# Module_DIO.net
KiCad netlist of a schematic drawn in EAGLE
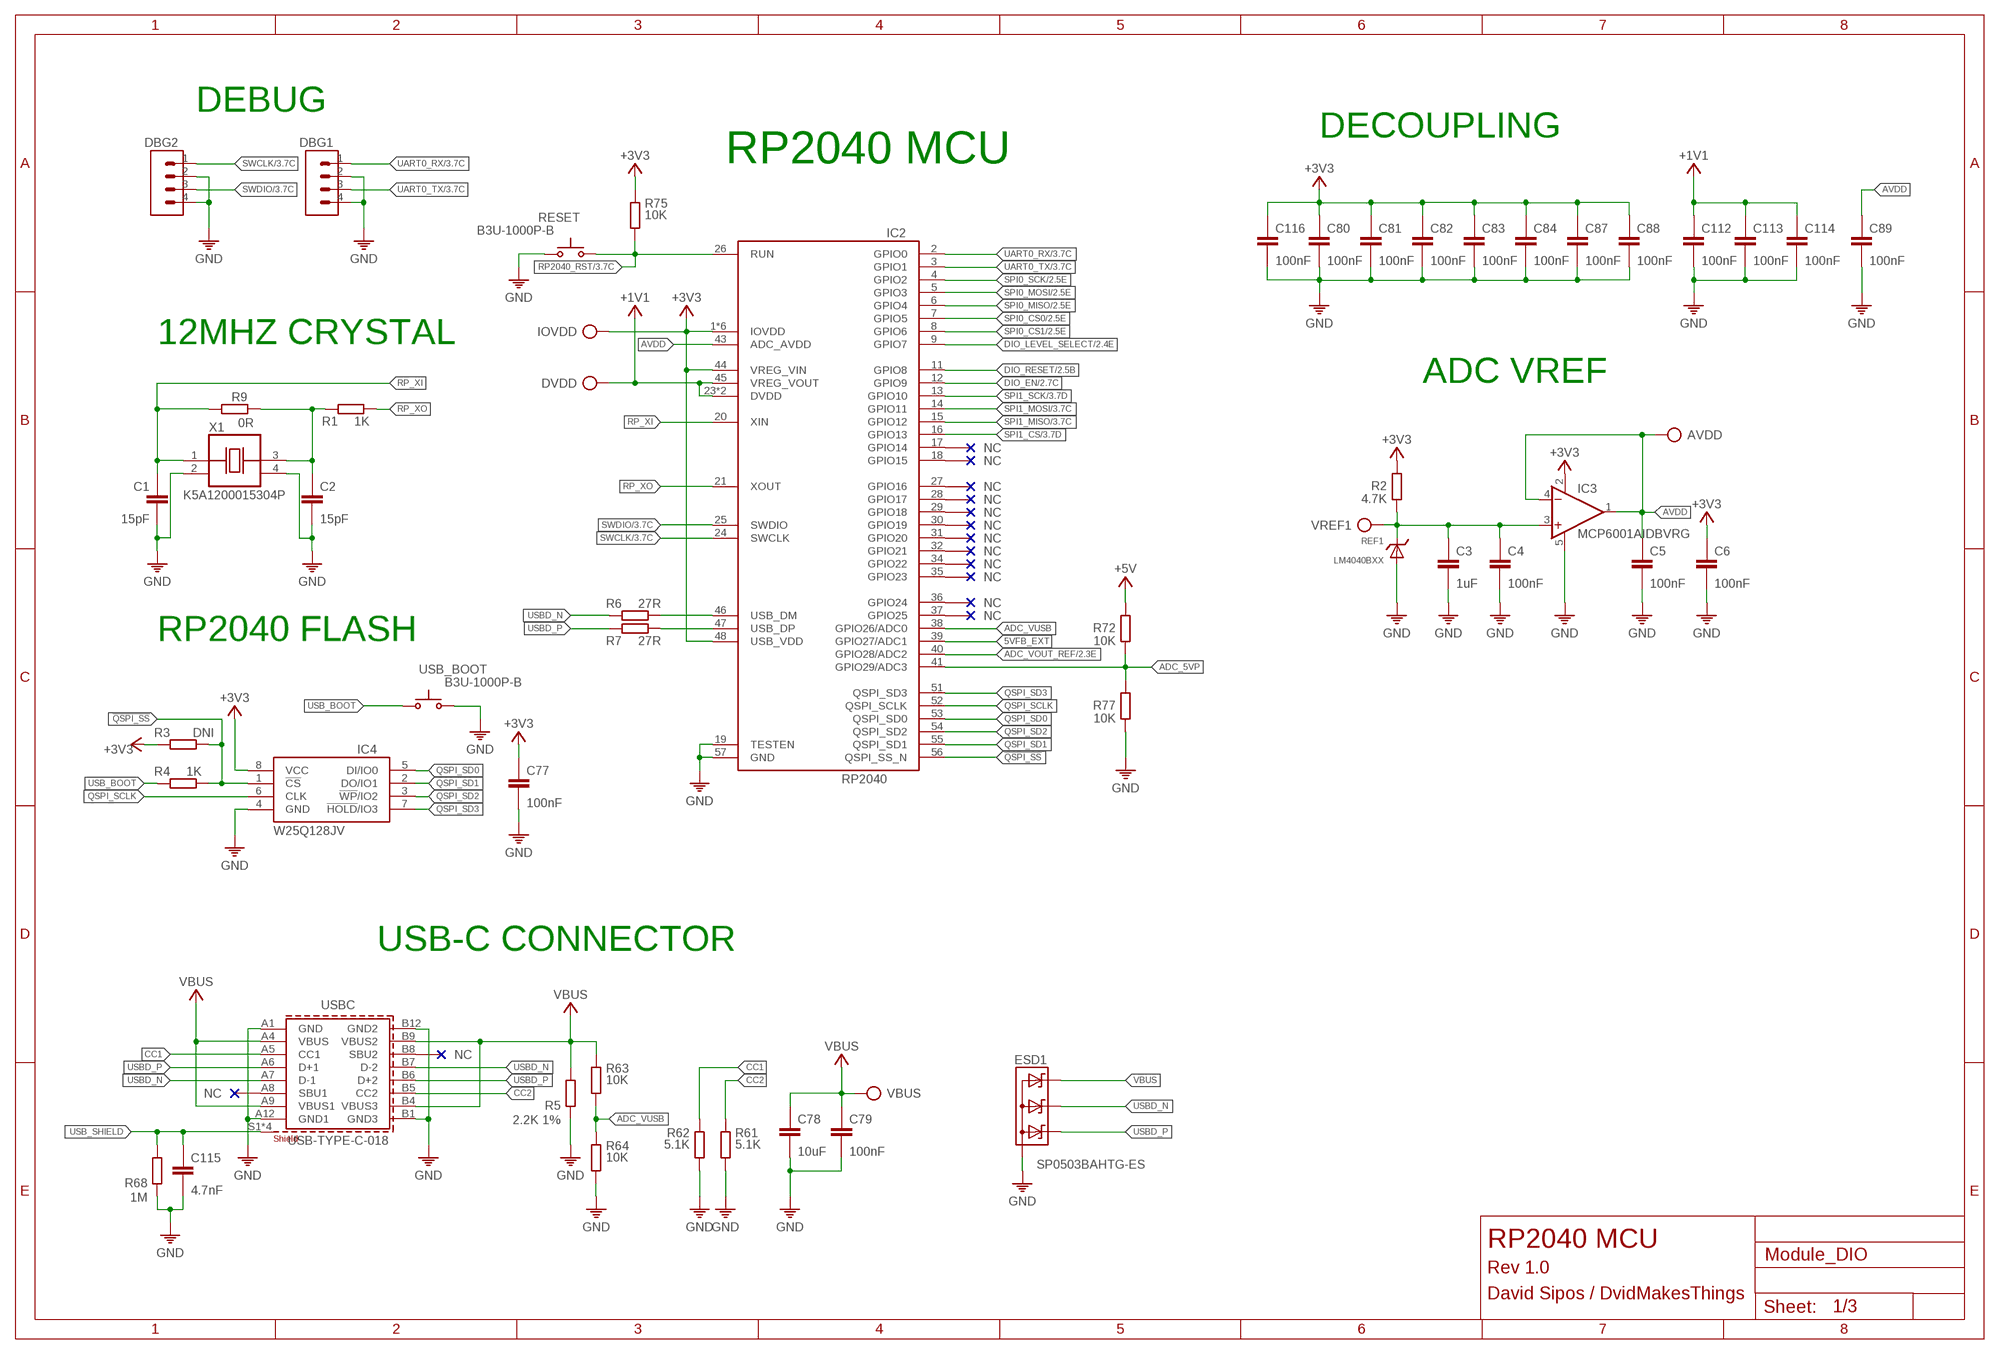
[diagram p0: schematic, sheet 1]
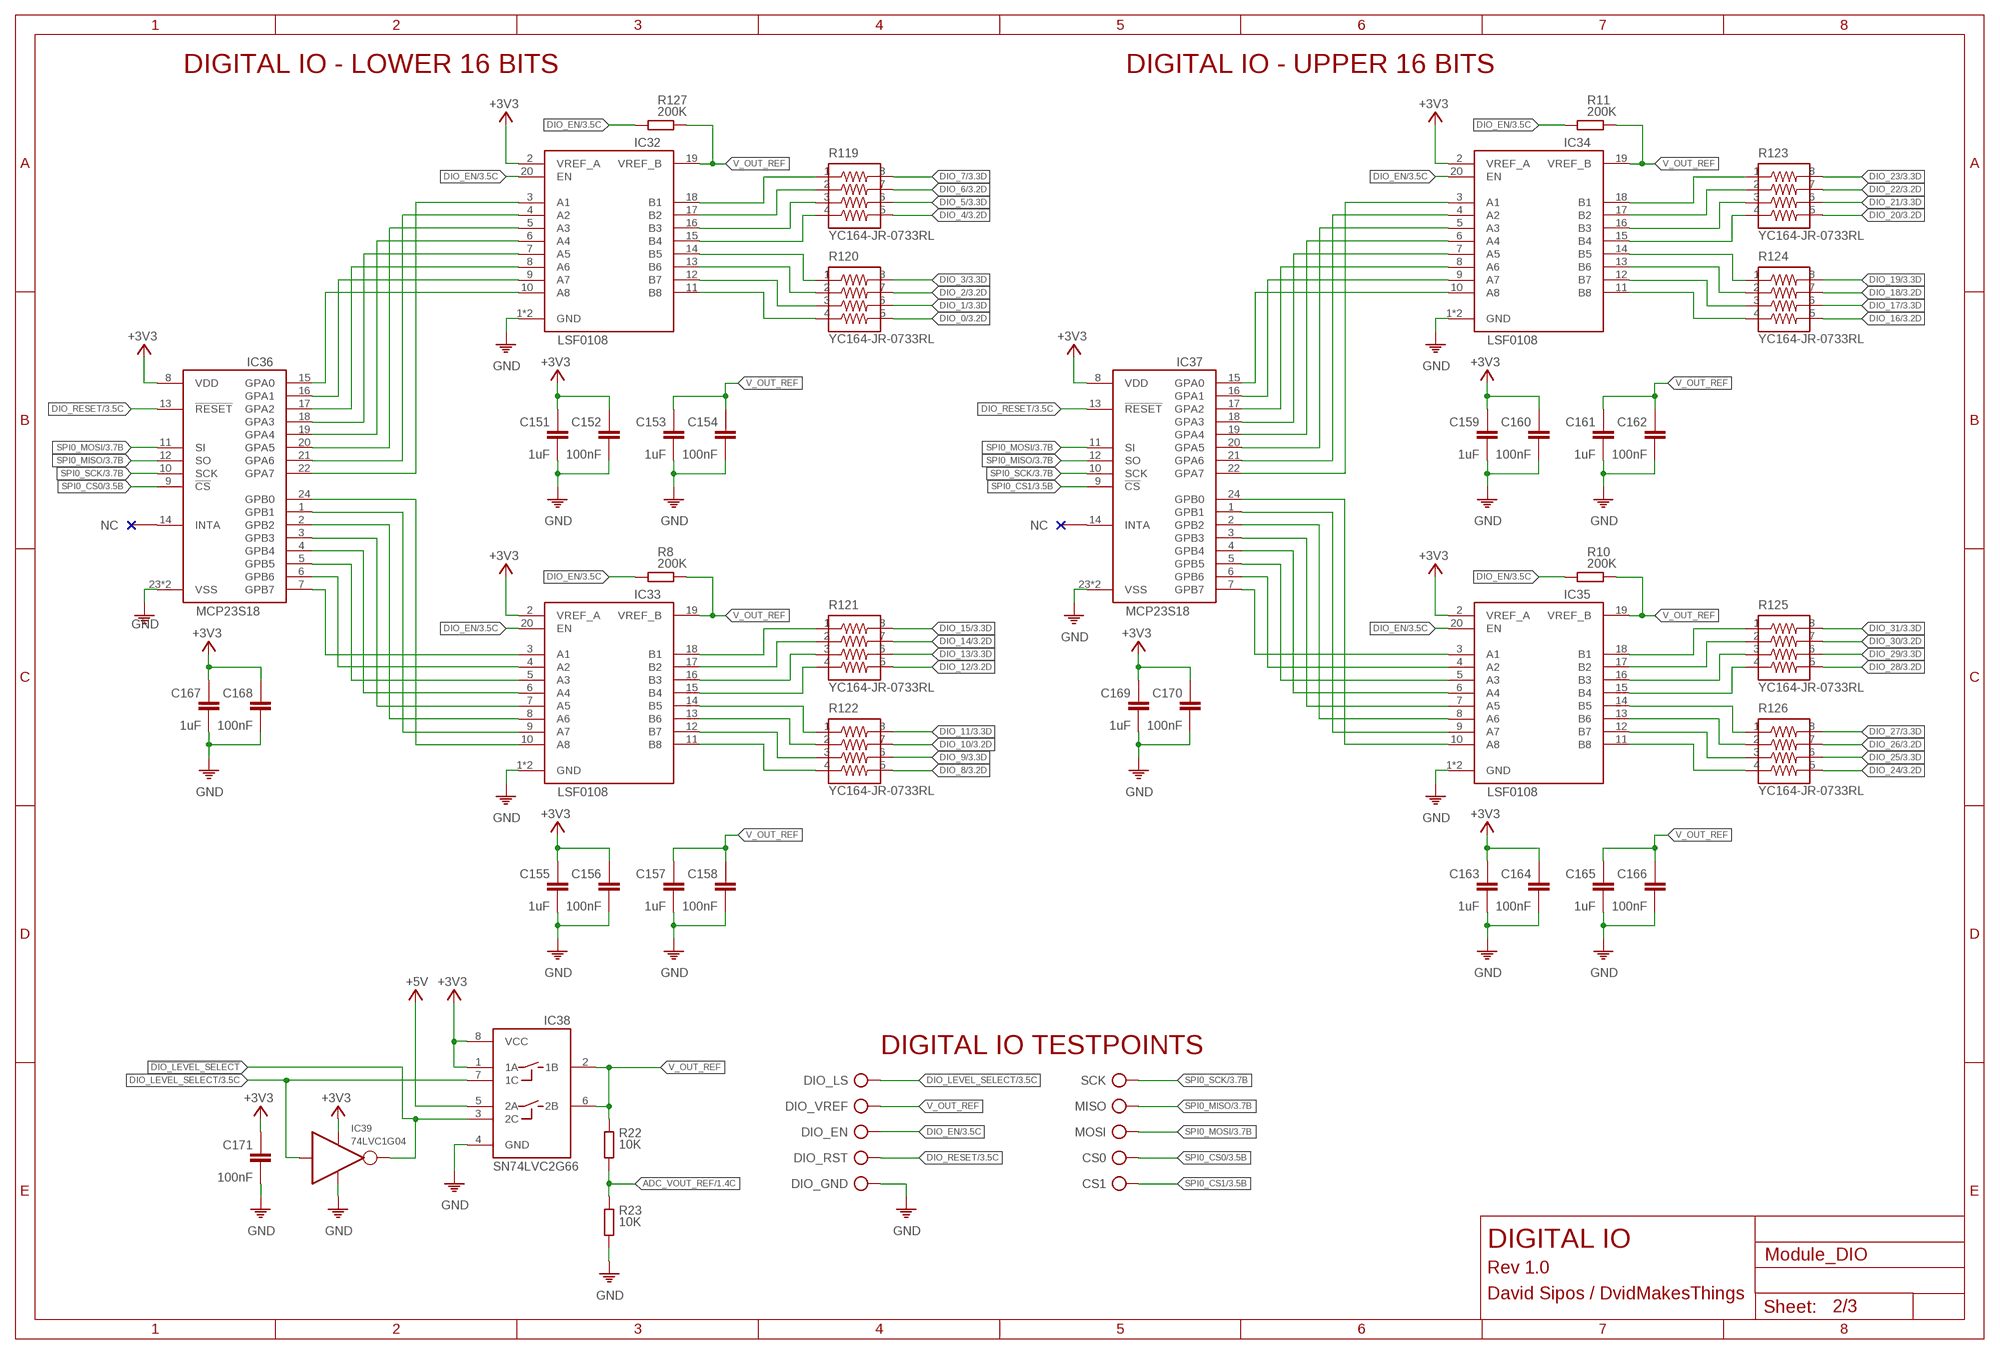
[diagram p1: schematic, sheet 2]
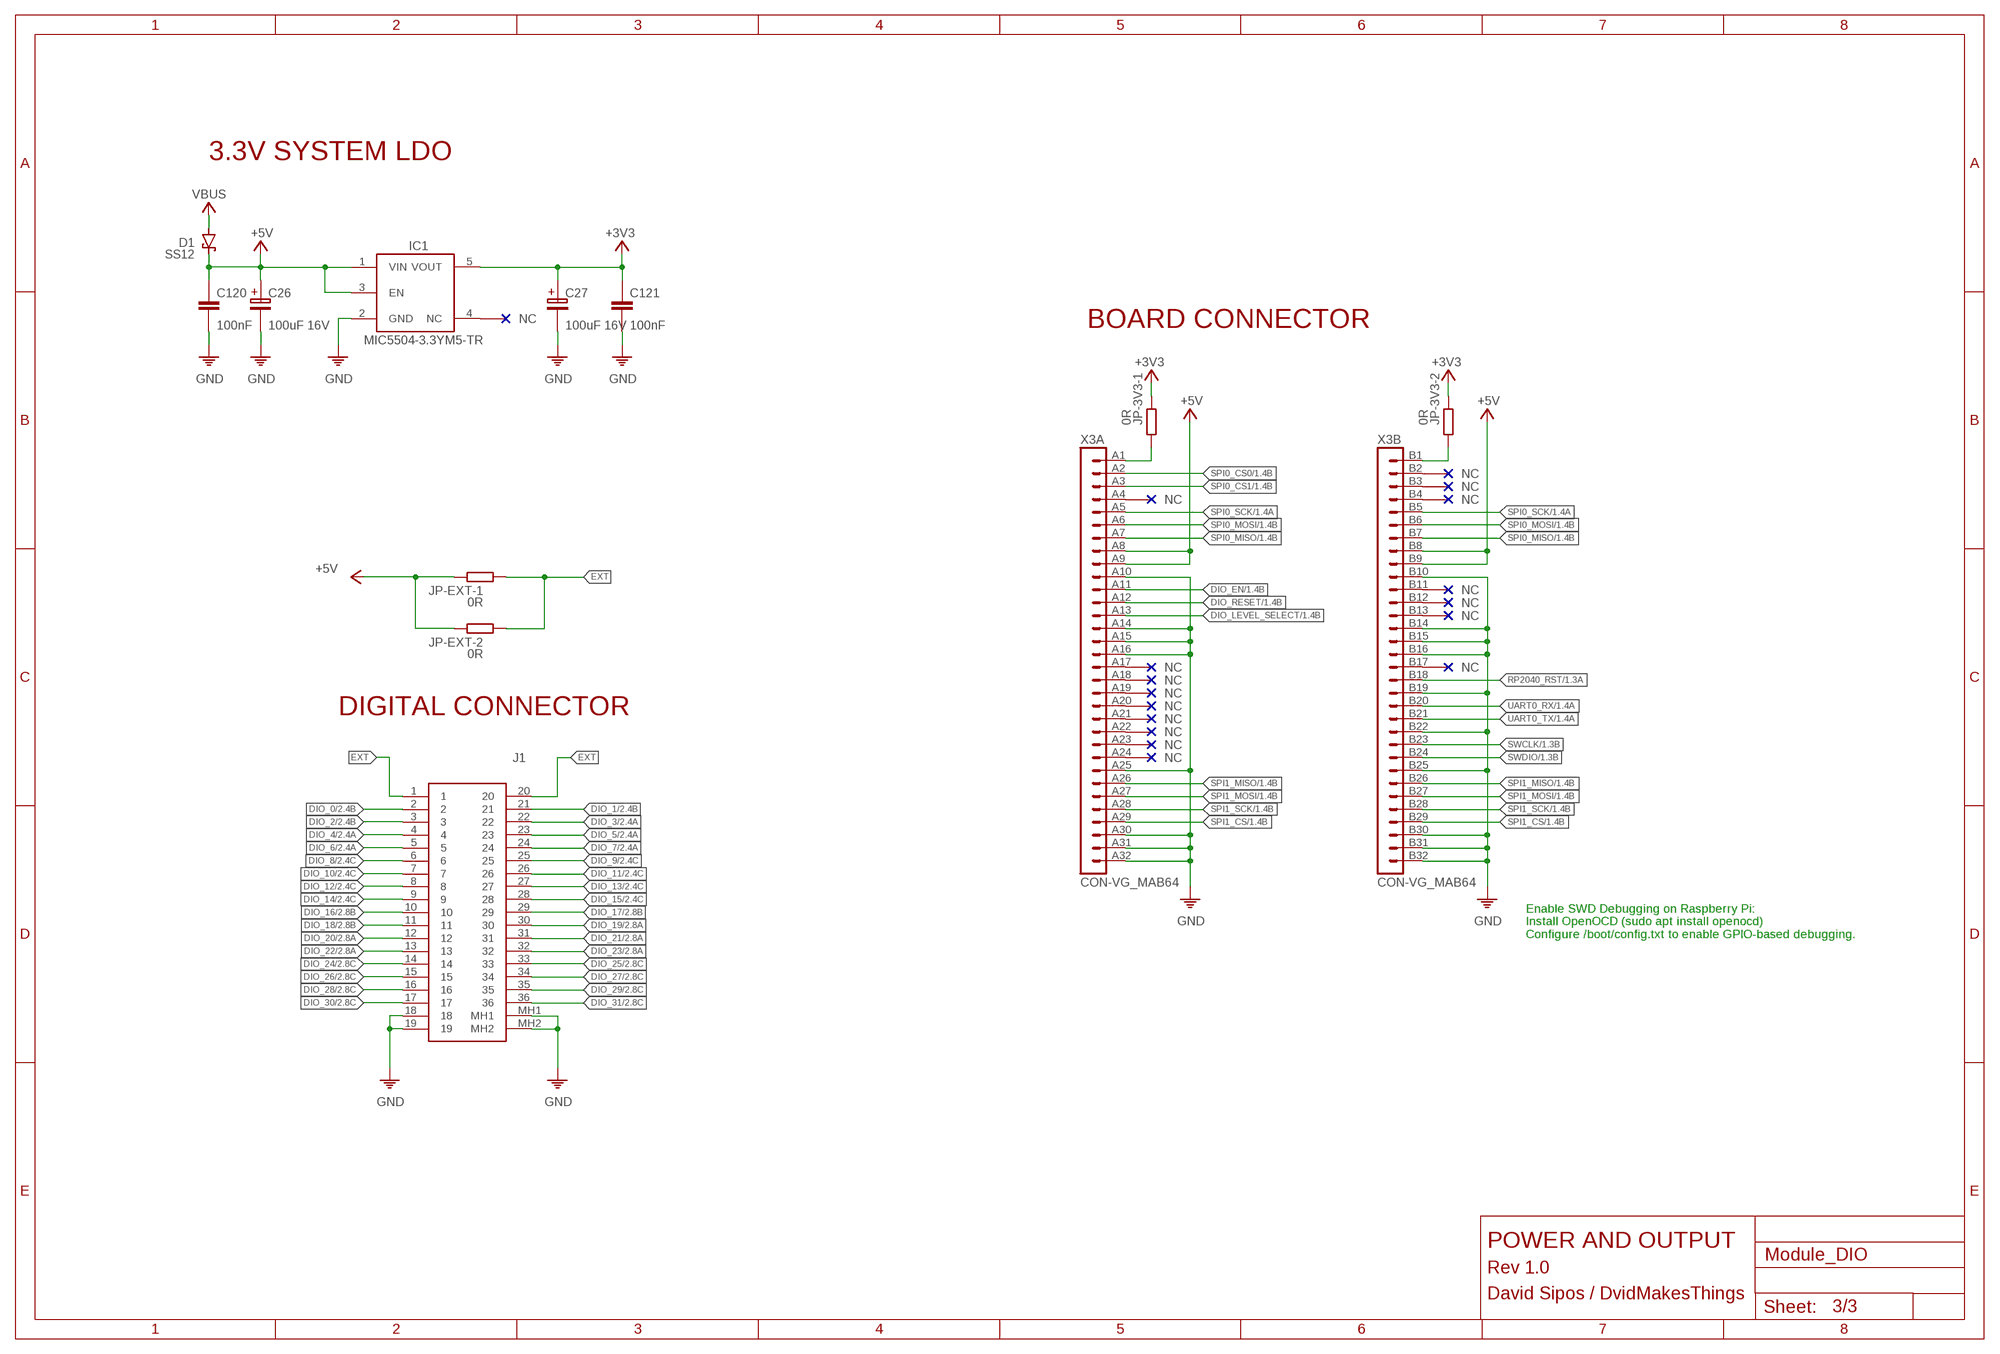
[diagram p2: schematic, sheet 3]

(export (version "E")
  (design (tool "Eeschema 10.0.6"))
  (components
    (comp (ref "C26")
      (value "100uF 16V")
      (footprint "eagle-import:100UF-16V")
      (libsource (lib "eagle-import") (part "CPOL"))
    )
    (comp (ref "C27")
      (value "100uF 16V")
      (footprint "eagle-import:100UF-16V")
      (libsource (lib "eagle-import") (part "CPOL"))
    )
    (comp (ref "C120")
      (value "100nF")
      (footprint "eagle-import:C0402")
      (libsource (lib "eagle-import") (part "C-0402"))
    )
    (comp (ref "C121")
      (value "100nF")
      (footprint "eagle-import:C0402")
      (libsource (lib "eagle-import") (part "C-0402"))
    )
    (comp (ref "D1")
      (value "SS12")
      (footprint "eagle-import:SMA")
      (fields
        (field (name "DIGIKEY_PART_NUMBER") "SS12FSCT-ND")
        (field (name "MANUFACTURER") "ON Semiconductor")
        (field (name "CREATED_BY") "PCBLayout.com")
      )
      (libsource (lib "eagle-import") (part "SS12"))
    )
    (comp (ref "IC1")
      (value "MIC5504-3.3YM5-TR")
      (footprint "eagle-import:SOT23-5")
      (libsource (lib "eagle-import") (part "MIC5504-3.3YM5-TR"))
    )
    (comp (ref "J1")
      (value "N10236-52B3PC")
      (footprint "eagle-import:MDB36")
      (libsource (lib "eagle-import") (part "N10236-52B3PC"))
    )
    (comp (ref "JP-3V3-1")
      (value "0R")
      (footprint "eagle-import:0603")
      (libsource (lib "eagle-import") (part "R0603"))
    )
    (comp (ref "JP-3V3-2")
      (value "0R")
      (footprint "eagle-import:0603")
      (libsource (lib "eagle-import") (part "R0603"))
    )
    (comp (ref "JP-EXT-1")
      (value "0R")
      (footprint "eagle-import:0603")
      (libsource (lib "eagle-import") (part "R0603"))
    )
    (comp (ref "JP-EXT-2")
      (value "0R")
      (footprint "eagle-import:0603")
      (libsource (lib "eagle-import") (part "R0603"))
    )
    (comp (ref "X3")
      (value "CON-VG_MAB64")
      (footprint "eagle-import:CON-VG_MAB64")
      (libsource (lib "eagle-import") (part "CON-VG_MAB64"))
    )
    (comp (ref "C151")
      (value "1uF")
      (footprint "eagle-import:C0402")
      (libsource (lib "eagle-import") (part "C-0402"))
    )
    (comp (ref "C152")
      (value "100nF")
      (footprint "eagle-import:C0402")
      (libsource (lib "eagle-import") (part "C-0402"))
    )
    (comp (ref "C153")
      (value "1uF")
      (footprint "eagle-import:C0402")
      (libsource (lib "eagle-import") (part "C-0402"))
    )
    (comp (ref "C154")
      (value "100nF")
      (footprint "eagle-import:C0402")
      (libsource (lib "eagle-import") (part "C-0402"))
    )
    (comp (ref "C155")
      (value "1uF")
      (footprint "eagle-import:C0402")
      (libsource (lib "eagle-import") (part "C-0402"))
    )
    (comp (ref "C156")
      (value "100nF")
      (footprint "eagle-import:C0402")
      (libsource (lib "eagle-import") (part "C-0402"))
    )
    (comp (ref "C157")
      (value "1uF")
      (footprint "eagle-import:C0402")
      (libsource (lib "eagle-import") (part "C-0402"))
    )
    (comp (ref "C158")
      (value "100nF")
      (footprint "eagle-import:C0402")
      (libsource (lib "eagle-import") (part "C-0402"))
    )
    (comp (ref "C159")
      (value "1uF")
      (footprint "eagle-import:C0402")
      (libsource (lib "eagle-import") (part "C-0402"))
    )
    (comp (ref "C160")
      (value "100nF")
      (footprint "eagle-import:C0402")
      (libsource (lib "eagle-import") (part "C-0402"))
    )
    (comp (ref "C161")
      (value "1uF")
      (footprint "eagle-import:C0402")
      (libsource (lib "eagle-import") (part "C-0402"))
    )
    (comp (ref "C162")
      (value "100nF")
      (footprint "eagle-import:C0402")
      (libsource (lib "eagle-import") (part "C-0402"))
    )
    (comp (ref "C163")
      (value "1uF")
      (footprint "eagle-import:C0402")
      (libsource (lib "eagle-import") (part "C-0402"))
    )
    (comp (ref "C164")
      (value "100nF")
      (footprint "eagle-import:C0402")
      (libsource (lib "eagle-import") (part "C-0402"))
    )
    (comp (ref "C165")
      (value "1uF")
      (footprint "eagle-import:C0402")
      (libsource (lib "eagle-import") (part "C-0402"))
    )
    (comp (ref "C166")
      (value "100nF")
      (footprint "eagle-import:C0402")
      (libsource (lib "eagle-import") (part "C-0402"))
    )
    (comp (ref "C167")
      (value "1uF")
      (footprint "eagle-import:C0402")
      (libsource (lib "eagle-import") (part "C-0402"))
    )
    (comp (ref "C168")
      (value "100nF")
      (footprint "eagle-import:C0402")
      (libsource (lib "eagle-import") (part "C-0402"))
    )
    (comp (ref "C169")
      (value "1uF")
      (footprint "eagle-import:C0402")
      (libsource (lib "eagle-import") (part "C-0402"))
    )
    (comp (ref "C170")
      (value "100nF")
      (footprint "eagle-import:C0402")
      (libsource (lib "eagle-import") (part "C-0402"))
    )
    (comp (ref "C171")
      (value "100nF")
      (footprint "eagle-import:C0603")
      (libsource (lib "eagle-import") (part "C-0603"))
    )
    (comp (ref "CS0") (value "TP") (footprint "eagle-import:TP") (libsource (lib "eagle-import") (part "TP")))
    (comp (ref "CS1") (value "TP") (footprint "eagle-import:TP") (libsource (lib "eagle-import") (part "TP")))
    (comp (ref "DIO_EN")
      (value "TP")
      (footprint "eagle-import:TP")
      (libsource (lib "eagle-import") (part "TP"))
    )
    (comp (ref "DIO_GND")
      (value "TP")
      (footprint "eagle-import:TP")
      (libsource (lib "eagle-import") (part "TP"))
    )
    (comp (ref "DIO_LS")
      (value "TP")
      (footprint "eagle-import:TP")
      (libsource (lib "eagle-import") (part "TP"))
    )
    (comp (ref "DIO_RST")
      (value "TP")
      (footprint "eagle-import:TP")
      (libsource (lib "eagle-import") (part "TP"))
    )
    (comp (ref "DIO_VREF")
      (value "TP")
      (footprint "eagle-import:TP")
      (libsource (lib "eagle-import") (part "TP"))
    )
    (comp (ref "IC32")
      (value "LSF0108")
      (footprint "eagle-import:VQFN20")
      (libsource (lib "eagle-import") (part "LSF0108-Q1"))
    )
    (comp (ref "IC33")
      (value "LSF0108")
      (footprint "eagle-import:VQFN20")
      (libsource (lib "eagle-import") (part "LSF0108-Q1"))
    )
    (comp (ref "IC34")
      (value "LSF0108")
      (footprint "eagle-import:VQFN20")
      (libsource (lib "eagle-import") (part "LSF0108-Q1"))
    )
    (comp (ref "IC35")
      (value "LSF0108")
      (footprint "eagle-import:VQFN20")
      (libsource (lib "eagle-import") (part "LSF0108-Q1"))
    )
    (comp (ref "IC36")
      (value "MCP23S18")
      (footprint "eagle-import:QFN50P400X400X100-25T265")
      (libsource (lib "eagle-import") (part "MCP23S18"))
    )
    (comp (ref "IC37")
      (value "MCP23S18")
      (footprint "eagle-import:QFN50P400X400X100-25T265")
      (libsource (lib "eagle-import") (part "MCP23S18"))
    )
    (comp (ref "IC38")
      (value "SN74LVC2G66")
      (footprint "eagle-import:SOP50P310X90-8N")
      (libsource (lib "eagle-import") (part "SN74LVC2G66"))
    )
    (comp (ref "IC39")
      (value "74LVC1G04")
      (footprint "eagle-import:SOT95P280X145-5N")
      (libsource (lib "eagle-import") (part "74LVC1G04"))
    )
    (comp (ref "MISO")
      (value "TP")
      (footprint "eagle-import:TP")
      (libsource (lib "eagle-import") (part "TP"))
    )
    (comp (ref "MOSI")
      (value "TP")
      (footprint "eagle-import:TP")
      (libsource (lib "eagle-import") (part "TP"))
    )
    (comp (ref "R8")
      (value "200K")
      (footprint "eagle-import:0402")
      (libsource (lib "eagle-import") (part "R0402"))
    )
    (comp (ref "R10")
      (value "200K")
      (footprint "eagle-import:0402")
      (libsource (lib "eagle-import") (part "R0402"))
    )
    (comp (ref "R11")
      (value "200K")
      (footprint "eagle-import:0402")
      (libsource (lib "eagle-import") (part "R0402"))
    )
    (comp (ref "R22")
      (value "10K")
      (footprint "eagle-import:0402")
      (libsource (lib "eagle-import") (part "R0402"))
    )
    (comp (ref "R23")
      (value "10K")
      (footprint "eagle-import:0402")
      (libsource (lib "eagle-import") (part "R0402"))
    )
    (comp (ref "R119")
      (value "YC164-JR-0733RL")
      (footprint "eagle-import:YC164-JR-0733RL")
      (fields (field (name "MANUFACTURER") "Yageo") (field (name "CREATED_BY") "PCBLayout.com"))
      (libsource (lib "eagle-import") (part "YC164-JR-0733RL"))
    )
    (comp (ref "R120")
      (value "YC164-JR-0733RL")
      (footprint "eagle-import:YC164-JR-0733RL")
      (fields (field (name "MANUFACTURER") "Yageo") (field (name "CREATED_BY") "PCBLayout.com"))
      (libsource (lib "eagle-import") (part "YC164-JR-0733RL"))
    )
    (comp (ref "R121")
      (value "YC164-JR-0733RL")
      (footprint "eagle-import:YC164-JR-0733RL")
      (fields (field (name "MANUFACTURER") "Yageo") (field (name "CREATED_BY") "PCBLayout.com"))
      (libsource (lib "eagle-import") (part "YC164-JR-0733RL"))
    )
    (comp (ref "R122")
      (value "YC164-JR-0733RL")
      (footprint "eagle-import:YC164-JR-0733RL")
      (fields (field (name "MANUFACTURER") "Yageo") (field (name "CREATED_BY") "PCBLayout.com"))
      (libsource (lib "eagle-import") (part "YC164-JR-0733RL"))
    )
    (comp (ref "R123")
      (value "YC164-JR-0733RL")
      (footprint "eagle-import:YC164-JR-0733RL")
      (fields (field (name "MANUFACTURER") "Yageo") (field (name "CREATED_BY") "PCBLayout.com"))
      (libsource (lib "eagle-import") (part "YC164-JR-0733RL"))
    )
    (comp (ref "R124")
      (value "YC164-JR-0733RL")
      (footprint "eagle-import:YC164-JR-0733RL")
      (fields (field (name "MANUFACTURER") "Yageo") (field (name "CREATED_BY") "PCBLayout.com"))
      (libsource (lib "eagle-import") (part "YC164-JR-0733RL"))
    )
    (comp (ref "R125")
      (value "YC164-JR-0733RL")
      (footprint "eagle-import:YC164-JR-0733RL")
      (fields (field (name "MANUFACTURER") "Yageo") (field (name "CREATED_BY") "PCBLayout.com"))
      (libsource (lib "eagle-import") (part "YC164-JR-0733RL"))
    )
    (comp (ref "R126")
      (value "YC164-JR-0733RL")
      (footprint "eagle-import:YC164-JR-0733RL")
      (fields (field (name "MANUFACTURER") "Yageo") (field (name "CREATED_BY") "PCBLayout.com"))
      (libsource (lib "eagle-import") (part "YC164-JR-0733RL"))
    )
    (comp (ref "R127")
      (value "200K")
      (footprint "eagle-import:0402")
      (libsource (lib "eagle-import") (part "R0402"))
    )
    (comp (ref "SCK") (value "TP") (footprint "eagle-import:TP") (libsource (lib "eagle-import") (part "TP")))
    (comp (ref "AVDD")
      (value "TP")
      (footprint "eagle-import:TP")
      (libsource (lib "eagle-import") (part "TP"))
    )
    (comp (ref "C1")
      (value "15pF")
      (footprint "eagle-import:C0402")
      (libsource (lib "eagle-import") (part "C-0402"))
    )
    (comp (ref "C2")
      (value "15pF")
      (footprint "eagle-import:C0402")
      (libsource (lib "eagle-import") (part "C-0402"))
    )
    (comp (ref "C3")
      (value "1uF")
      (footprint "eagle-import:C0402")
      (libsource (lib "eagle-import") (part "C-0402"))
    )
    (comp (ref "C4")
      (value "100nF")
      (footprint "eagle-import:C0402")
      (libsource (lib "eagle-import") (part "C-0402"))
    )
    (comp (ref "C5")
      (value "100nF")
      (footprint "eagle-import:C0402")
      (libsource (lib "eagle-import") (part "C-0402"))
    )
    (comp (ref "C6")
      (value "100nF")
      (footprint "eagle-import:C0402")
      (libsource (lib "eagle-import") (part "C-0402"))
    )
    (comp (ref "C77")
      (value "100nF")
      (footprint "eagle-import:C0402")
      (libsource (lib "eagle-import") (part "C-0402"))
    )
    (comp (ref "C78")
      (value "10uF")
      (footprint "eagle-import:0805")
      (libsource (lib "eagle-import") (part "C0805"))
    )
    (comp (ref "C79")
      (value "100nF")
      (footprint "eagle-import:0402")
      (libsource (lib "eagle-import") (part "C0402"))
    )
    (comp (ref "C80")
      (value "100nF")
      (footprint "eagle-import:C0402")
      (libsource (lib "eagle-import") (part "C-0402"))
    )
    (comp (ref "C81")
      (value "100nF")
      (footprint "eagle-import:C0402")
      (libsource (lib "eagle-import") (part "C-0402"))
    )
    (comp (ref "C82")
      (value "100nF")
      (footprint "eagle-import:C0402")
      (libsource (lib "eagle-import") (part "C-0402"))
    )
    (comp (ref "C83")
      (value "100nF")
      (footprint "eagle-import:C0402")
      (libsource (lib "eagle-import") (part "C-0402"))
    )
    (comp (ref "C84")
      (value "100nF")
      (footprint "eagle-import:C0402")
      (libsource (lib "eagle-import") (part "C-0402"))
    )
    (comp (ref "C87")
      (value "100nF")
      (footprint "eagle-import:C0402")
      (libsource (lib "eagle-import") (part "C-0402"))
    )
    (comp (ref "C88")
      (value "100nF")
      (footprint "eagle-import:C0402")
      (libsource (lib "eagle-import") (part "C-0402"))
    )
    (comp (ref "C89")
      (value "100nF")
      (footprint "eagle-import:C0402")
      (libsource (lib "eagle-import") (part "C-0402"))
    )
    (comp (ref "C112")
      (value "100nF")
      (footprint "eagle-import:C0402")
      (libsource (lib "eagle-import") (part "C-0402"))
    )
    (comp (ref "C113")
      (value "100nF")
      (footprint "eagle-import:C0402")
      (libsource (lib "eagle-import") (part "C-0402"))
    )
    (comp (ref "C114")
      (value "100nF")
      (footprint "eagle-import:C0402")
      (libsource (lib "eagle-import") (part "C-0402"))
    )
    (comp (ref "C115")
      (value "4.7nF")
      (footprint "eagle-import:0402")
      (libsource (lib "eagle-import") (part "C0402"))
    )
    (comp (ref "C116")
      (value "100nF")
      (footprint "eagle-import:C0402")
      (libsource (lib "eagle-import") (part "C-0402"))
    )
    (comp (ref "DBG1")
      (value "CON-1X4")
      (footprint "eagle-import:1X4")
      (libsource (lib "eagle-import") (part "CON-1X4"))
    )
    (comp (ref "DBG2")
      (value "CON-1X4")
      (footprint "eagle-import:1X4")
      (libsource (lib "eagle-import") (part "CON-1X4"))
    )
    (comp (ref "DVDD")
      (value "TP")
      (footprint "eagle-import:TP")
      (libsource (lib "eagle-import") (part "TP"))
    )
    (comp (ref "ESD1")
      (value "SP0503BAHTG-ES")
      (footprint "eagle-import:SOT143")
      (libsource (lib "eagle-import") (part "SP0503BAHT"))
    )
    (comp (ref "IC2")
      (value "RP2040")
      (footprint "eagle-import:QFN40P700X700X100-57T510")
      (libsource (lib "eagle-import") (part "RP2040"))
    )
    (comp (ref "IC3")
      (value "MCP6001AIDBVRG")
      (footprint "eagle-import:SOT23-5")
      (libsource (lib "eagle-import") (part "MCP6001RT"))
    )
    (comp (ref "IC4")
      (value "W25Q128JVPIQ")
      (footprint "eagle-import:SON127P600X500X75-8N")
      (libsource (lib "eagle-import") (part "W25Q128JVP"))
    )
    (comp (ref "IOVDD")
      (value "TP")
      (footprint "eagle-import:TP")
      (libsource (lib "eagle-import") (part "TP"))
    )
    (comp (ref "R1")
      (value "1K")
      (footprint "eagle-import:0402")
      (libsource (lib "eagle-import") (part "R0402"))
    )
    (comp (ref "R2")
      (value "4.7K")
      (footprint "eagle-import:0402")
      (libsource (lib "eagle-import") (part "R0402"))
    )
    (comp (ref "R3")
      (value "DNI")
      (footprint "eagle-import:0402")
      (libsource (lib "eagle-import") (part "R0402"))
    )
    (comp (ref "R4")
      (value "1K")
      (footprint "eagle-import:0402")
      (libsource (lib "eagle-import") (part "R0402"))
    )
    (comp (ref "R5")
      (value "2.2K 1%")
      (footprint "eagle-import:0402")
      (libsource (lib "eagle-import") (part "ds_passive_46685041_R0402"))
    )
    (comp (ref "R6")
      (value "27R")
      (footprint "eagle-import:0402")
      (libsource (lib "eagle-import") (part "R0402"))
    )
    (comp (ref "R7")
      (value "27R")
      (footprint "eagle-import:0402")
      (libsource (lib "eagle-import") (part "R0402"))
    )
    (comp (ref "R9")
      (value "0R")
      (footprint "eagle-import:0402")
      (libsource (lib "eagle-import") (part "R0402"))
    )
    (comp (ref "R61")
      (value "5.1K")
      (footprint "eagle-import:0402")
      (libsource (lib "eagle-import") (part "ds_passive_46685041_R0402"))
    )
    (comp (ref "R62")
      (value "5.1K")
      (footprint "eagle-import:0402")
      (libsource (lib "eagle-import") (part "ds_passive_46685041_R0402"))
    )
    (comp (ref "R63")
      (value "10K")
      (footprint "eagle-import:0402")
      (libsource (lib "eagle-import") (part "ds_passive_46685041_R0402"))
    )
    (comp (ref "R64")
      (value "10K")
      (footprint "eagle-import:0402")
      (libsource (lib "eagle-import") (part "ds_passive_46685041_R0402"))
    )
    (comp (ref "R68")
      (value "1M")
      (footprint "eagle-import:0402")
      (libsource (lib "eagle-import") (part "ds_passive_46685041_R0402"))
    )
    (comp (ref "R72")
      (value "10K")
      (footprint "eagle-import:0402")
      (libsource (lib "eagle-import") (part "R0402"))
    )
    (comp (ref "R75")
      (value "10K")
      (footprint "eagle-import:0402")
      (libsource (lib "eagle-import") (part "ds_passive_46685041_R0402"))
    )
    (comp (ref "R77")
      (value "10K")
      (footprint "eagle-import:0402")
      (libsource (lib "eagle-import") (part "R0402"))
    )
    (comp (ref "REF1")
      (value "LM4040BXX")
      (footprint "eagle-import:SOT23")
      (libsource (lib "eagle-import") (part "LM4040BXX"))
    )
    (comp (ref "RESET")
      (value "B3U-1000P-B")
      (footprint "eagle-import:SWITCH-OMRON_B3U-1000P")
      (libsource (lib "eagle-import") (part "SWITCH-OMRON_B3U-1000P"))
    )
    (comp (ref "USBC")
      (value "USB-TYPE-C-018")
      (footprint "eagle-import:629722000214")
      (libsource (lib "eagle-import") (part "629722000214"))
    )
    (comp (ref "USB_BOOT")
      (value "B3U-1000P-B")
      (footprint "eagle-import:SWITCH-OMRON_B3U-1000P")
      (libsource (lib "eagle-import") (part "SWITCH-OMRON_B3U-1000P"))
    )
    (comp (ref "VBUS")
      (value "TP")
      (footprint "eagle-import:TP")
      (libsource (lib "eagle-import") (part "TP"))
    )
    (comp (ref "VREF1")
      (value "TP")
      (footprint "eagle-import:TP")
      (libsource (lib "eagle-import") (part "TP"))
    )
    (comp (ref "X1")
      (value "K5A1200015304P")
      (footprint "eagle-import:OSCCC500X320X130")
      (libsource (lib "eagle-import") (part "CRYSTAL"))
    )
  )
  (nets
    (net (code "1") (name "+1V1") (class "Default")
      (node (ref "C112") (pin "1") (pinfunction "1_1") (pintype "passive"))
      (node (ref "C113") (pin "1") (pinfunction "1_1") (pintype "passive"))
      (node (ref "C114") (pin "1") (pinfunction "1_1") (pintype "passive"))
      (node (ref "DVDD") (pin "TP") (pinfunction "P$1_TP") (pintype "bidirectional"))
      (node (ref "IC2") (pin "23") (pinfunction "DVDD_23") (pintype "bidirectional"))
      (node (ref "IC2") (pin "45") (pinfunction "VREG_VOUT_45") (pintype "bidirectional"))
      (node (ref "IC2") (pin "50") (pinfunction "DVDD_50") (pintype "bidirectional"))
    )
    (net (code "2") (name "+3V3") (class "Default")
      (node (ref "C116") (pin "1") (pinfunction "1_1") (pintype "passive"))
      (node (ref "C121") (pin "1") (pinfunction "1_1") (pintype "passive"))
      (node (ref "C151") (pin "1") (pinfunction "1_1") (pintype "passive"))
      (node (ref "C152") (pin "1") (pinfunction "1_1") (pintype "passive"))
      (node (ref "C155") (pin "1") (pinfunction "1_1") (pintype "passive"))
      (node (ref "C156") (pin "1") (pinfunction "1_1") (pintype "passive"))
      (node (ref "C159") (pin "1") (pinfunction "1_1") (pintype "passive"))
      (node (ref "C160") (pin "1") (pinfunction "1_1") (pintype "passive"))
      (node (ref "C163") (pin "1") (pinfunction "1_1") (pintype "passive"))
      (node (ref "C164") (pin "1") (pinfunction "1_1") (pintype "passive"))
      (node (ref "C167") (pin "1") (pinfunction "1_1") (pintype "passive"))
      (node (ref "C168") (pin "1") (pinfunction "1_1") (pintype "passive"))
      (node (ref "C169") (pin "1") (pinfunction "1_1") (pintype "passive"))
      (node (ref "C170") (pin "1") (pinfunction "1_1") (pintype "passive"))
      (node (ref "C171") (pin "1") (pinfunction "1_1") (pintype "passive"))
      (node (ref "C27") (pin "1") (pinfunction "1_1") (pintype "passive"))
      (node (ref "C6") (pin "1") (pinfunction "1_1") (pintype "passive"))
      (node (ref "C77") (pin "1") (pinfunction "1_1") (pintype "passive"))
      (node (ref "C80") (pin "1") (pinfunction "1_1") (pintype "passive"))
      (node (ref "C81") (pin "1") (pinfunction "1_1") (pintype "passive"))
      (node (ref "C82") (pin "1") (pinfunction "1_1") (pintype "passive"))
      (node (ref "C83") (pin "1") (pinfunction "1_1") (pintype "passive"))
      (node (ref "C84") (pin "1") (pinfunction "1_1") (pintype "passive"))
      (node (ref "C87") (pin "1") (pinfunction "1_1") (pintype "passive"))
      (node (ref "C88") (pin "1") (pinfunction "1_1") (pintype "passive"))
      (node (ref "IC1") (pin "5") (pinfunction "VOUT_5") (pintype "bidirectional"))
      (node (ref "IC2") (pin "1") (pinfunction "IOVDD_1") (pintype "bidirectional"))
      (node (ref "IC2") (pin "10") (pinfunction "IOVDD_10") (pintype "bidirectional"))
      (node (ref "IC2") (pin "22") (pinfunction "IOVDD_22") (pintype "bidirectional"))
      (node (ref "IC2") (pin "33") (pinfunction "IOVDD_33") (pintype "bidirectional"))
      (node (ref "IC2") (pin "42") (pinfunction "IOVDD_42") (pintype "bidirectional"))
      (node (ref "IC2") (pin "44") (pinfunction "VREG_VIN_44") (pintype "bidirectional"))
      (node (ref "IC2") (pin "48") (pinfunction "USB_VDD_48") (pintype "bidirectional"))
      (node (ref "IC2") (pin "49") (pinfunction "IOVDD_49") (pintype "bidirectional"))
      (node (ref "IC3") (pin "2") (pinfunction "V+_2") (pintype "power_in"))
      (node (ref "IC32") (pin "2") (pinfunction "VREF_A_2") (pintype "power_in"))
      (node (ref "IC33") (pin "2") (pinfunction "VREF_A_2") (pintype "power_in"))
      (node (ref "IC34") (pin "2") (pinfunction "VREF_A_2") (pintype "power_in"))
      (node (ref "IC35") (pin "2") (pinfunction "VREF_A_2") (pintype "power_in"))
      (node (ref "IC36") (pin "8") (pinfunction "VDD_8") (pintype "power_in"))
      (node (ref "IC37") (pin "8") (pinfunction "VDD_8") (pintype "power_in"))
      (node (ref "IC38") (pin "1") (pinfunction "1A_1") (pintype "bidirectional"))
      (node (ref "IC38") (pin "8") (pinfunction "VCC_8") (pintype "power_in"))
      (node (ref "IC39") (pin "5") (pinfunction "V+_5") (pintype "bidirectional"))
      (node (ref "IC4") (pin "8") (pinfunction "VCC_8") (pintype "power_in"))
      (node (ref "IOVDD") (pin "TP") (pinfunction "P$1_TP") (pintype "bidirectional"))
      (node (ref "JP-3V3-1") (pin "1") (pinfunction "1_1") (pintype "passive"))
      (node (ref "JP-3V3-2") (pin "1") (pinfunction "1_1") (pintype "passive"))
      (node (ref "R2") (pin "2") (pinfunction "2_2") (pintype "passive"))
      (node (ref "R3") (pin "2") (pinfunction "2_2") (pintype "passive"))
      (node (ref "R75") (pin "1") (pinfunction "1_1") (pintype "passive"))
    )
    (net (code "3") (name "+5V") (class "Default")
      (node (ref "C120") (pin "1") (pinfunction "1_1") (pintype "passive"))
      (node (ref "C26") (pin "1") (pinfunction "1_1") (pintype "passive"))
      (node (ref "D1") (pin "C") (pinfunction "C_C") (pintype "passive"))
      (node (ref "IC1") (pin "1") (pinfunction "VIN_1") (pintype "bidirectional"))
      (node (ref "IC1") (pin "3") (pinfunction "EN_3") (pintype "bidirectional"))
      (node (ref "IC38") (pin "5") (pinfunction "2A_5") (pintype "bidirectional"))
      (node (ref "JP-EXT-1") (pin "1") (pinfunction "1_1") (pintype "passive"))
      (node (ref "JP-EXT-2") (pin "1") (pinfunction "1_1") (pintype "passive"))
      (node (ref "R72") (pin "2") (pinfunction "2_2") (pintype "passive"))
      (node (ref "X3") (pin "A8") (pinfunction "8_A8") (pintype "passive"))
      (node (ref "X3") (pin "A9") (pinfunction "9_A9") (pintype "passive"))
      (node (ref "X3") (pin "B8") (pinfunction "8_B8") (pintype "passive"))
      (node (ref "X3") (pin "B9") (pinfunction "9_B9") (pintype "passive"))
    )
    (net (code "4") (name "5VFB_EXT") (class "Default")
      (node (ref "IC2") (pin "39") (pinfunction "GPIO27/ADC1_39") (pintype "bidirectional"))
    )
    (net (code "5") (name "ADC_5VP") (class "Default")
      (node (ref "IC2") (pin "41") (pinfunction "GPIO29/ADC3_41") (pintype "bidirectional"))
      (node (ref "R72") (pin "1") (pinfunction "1_1") (pintype "passive"))
      (node (ref "R77") (pin "2") (pinfunction "2_2") (pintype "passive"))
    )
    (net (code "6") (name "ADC_VOUT_REF") (class "Default")
      (node (ref "IC2") (pin "40") (pinfunction "GPIO28/ADC2_40") (pintype "bidirectional"))
      (node (ref "R22") (pin "2") (pinfunction "2_2") (pintype "passive"))
      (node (ref "R23") (pin "1") (pinfunction "1_1") (pintype "passive"))
    )
    (net (code "7") (name "ADC_VUSB") (class "Default")
      (node (ref "IC2") (pin "38") (pinfunction "GPIO26/ADC0_38") (pintype "bidirectional"))
      (node (ref "R63") (pin "2") (pinfunction "2_2") (pintype "passive"))
      (node (ref "R64") (pin "1") (pinfunction "1_1") (pintype "passive"))
    )
    (net (code "8") (name "AVDD") (class "Default")
      (node (ref "AVDD") (pin "TP") (pinfunction "P$1_TP") (pintype "bidirectional"))
      (node (ref "C5") (pin "1") (pinfunction "1_1") (pintype "passive"))
      (node (ref "C89") (pin "1") (pinfunction "1_1") (pintype "passive"))
      (node (ref "IC2") (pin "43") (pinfunction "ADC_AVDD_43") (pintype "bidirectional"))
      (node (ref "IC3") (pin "1") (pinfunction "OUT_1") (pintype "output"))
      (node (ref "IC3") (pin "4") (pinfunction "-IN_4") (pintype "input"))
    )
    (net (code "9") (name "CC1") (class "Default")
      (node (ref "R62") (pin "1") (pinfunction "1_1") (pintype "passive"))
      (node (ref "USBC") (pin "A5") (pinfunction "CC1_A5") (pintype "passive"))
    )
    (net (code "10") (name "CC2") (class "Default")
      (node (ref "R61") (pin "1") (pinfunction "1_1") (pintype "passive"))
      (node (ref "USBC") (pin "B5") (pinfunction "CC2_B5") (pintype "passive"))
    )
    (net (code "11") (name "DIO_0") (class "Default")
      (node (ref "J1") (pin "2") (pinfunction "2_2") (pintype "bidirectional"))
      (node (ref "R120") (pin "5") (pinfunction "5_5") (pintype "passive"))
    )
    (net (code "12") (name "DIO_1") (class "Default")
      (node (ref "J1") (pin "21") (pinfunction "21_21") (pintype "bidirectional"))
      (node (ref "R120") (pin "6") (pinfunction "6_6") (pintype "passive"))
    )
    (net (code "13") (name "DIO_2") (class "Default")
      (node (ref "J1") (pin "3") (pinfunction "3_3") (pintype "bidirectional"))
      (node (ref "R120") (pin "7") (pinfunction "7_7") (pintype "passive"))
    )
    (net (code "14") (name "DIO_3") (class "Default")
      (node (ref "J1") (pin "22") (pinfunction "22_22") (pintype "bidirectional"))
      (node (ref "R120") (pin "8") (pinfunction "8_8") (pintype "passive"))
    )
    (net (code "15") (name "DIO_4") (class "Default")
      (node (ref "J1") (pin "4") (pinfunction "4_4") (pintype "bidirectional"))
      (node (ref "R119") (pin "5") (pinfunction "5_5") (pintype "passive"))
    )
    (net (code "16") (name "DIO_5") (class "Default")
      (node (ref "J1") (pin "23") (pinfunction "23_23") (pintype "bidirectional"))
      (node (ref "R119") (pin "6") (pinfunction "6_6") (pintype "passive"))
    )
    (net (code "17") (name "DIO_6") (class "Default")
      (node (ref "J1") (pin "5") (pinfunction "5_5") (pintype "bidirectional"))
      (node (ref "R119") (pin "7") (pinfunction "7_7") (pintype "passive"))
    )
    (net (code "18") (name "DIO_7") (class "Default")
      (node (ref "J1") (pin "24") (pinfunction "24_24") (pintype "bidirectional"))
      (node (ref "R119") (pin "8") (pinfunction "8_8") (pintype "passive"))
    )
    (net (code "19") (name "DIO_8") (class "Default")
      (node (ref "J1") (pin "6") (pinfunction "6_6") (pintype "bidirectional"))
      (node (ref "R122") (pin "5") (pinfunction "5_5") (pintype "passive"))
    )
    (net (code "20") (name "DIO_9") (class "Default")
      (node (ref "J1") (pin "25") (pinfunction "25_25") (pintype "bidirectional"))
      (node (ref "R122") (pin "6") (pinfunction "6_6") (pintype "passive"))
    )
    (net (code "21") (name "DIO_10") (class "Default")
      (node (ref "J1") (pin "7") (pinfunction "7_7") (pintype "bidirectional"))
      (node (ref "R122") (pin "7") (pinfunction "7_7") (pintype "passive"))
    )
    (net (code "22") (name "DIO_11") (class "Default")
      (node (ref "J1") (pin "26") (pinfunction "26_26") (pintype "bidirectional"))
      (node (ref "R122") (pin "8") (pinfunction "8_8") (pintype "passive"))
    )
    (net (code "23") (name "DIO_12") (class "Default")
      (node (ref "J1") (pin "8") (pinfunction "8_8") (pintype "bidirectional"))
      (node (ref "R121") (pin "5") (pinfunction "5_5") (pintype "passive"))
    )
    (net (code "24") (name "DIO_13") (class "Default")
      (node (ref "J1") (pin "27") (pinfunction "27_27") (pintype "bidirectional"))
      (node (ref "R121") (pin "6") (pinfunction "6_6") (pintype "passive"))
    )
    (net (code "25") (name "DIO_14") (class "Default")
      (node (ref "J1") (pin "9") (pinfunction "9_9") (pintype "bidirectional"))
      (node (ref "R121") (pin "7") (pinfunction "7_7") (pintype "passive"))
    )
    (net (code "26") (name "DIO_15") (class "Default")
      (node (ref "J1") (pin "28") (pinfunction "28_28") (pintype "bidirectional"))
      (node (ref "R121") (pin "8") (pinfunction "8_8") (pintype "passive"))
    )
    (net (code "27") (name "DIO_16") (class "Default")
      (node (ref "J1") (pin "10") (pinfunction "10_10") (pintype "bidirectional"))
      (node (ref "R124") (pin "5") (pinfunction "5_5") (pintype "passive"))
    )
    (net (code "28") (name "DIO_17") (class "Default")
      (node (ref "J1") (pin "29") (pinfunction "29_29") (pintype "bidirectional"))
      (node (ref "R124") (pin "6") (pinfunction "6_6") (pintype "passive"))
    )
    (net (code "29") (name "DIO_18") (class "Default")
      (node (ref "J1") (pin "11") (pinfunction "11_11") (pintype "bidirectional"))
      (node (ref "R124") (pin "7") (pinfunction "7_7") (pintype "passive"))
    )
    (net (code "30") (name "DIO_19") (class "Default")
      (node (ref "J1") (pin "30") (pinfunction "30_30") (pintype "bidirectional"))
      (node (ref "R124") (pin "8") (pinfunction "8_8") (pintype "passive"))
    )
    (net (code "31") (name "DIO_20") (class "Default")
      (node (ref "J1") (pin "12") (pinfunction "12_12") (pintype "bidirectional"))
      (node (ref "R123") (pin "5") (pinfunction "5_5") (pintype "passive"))
    )
    (net (code "32") (name "DIO_21") (class "Default")
      (node (ref "J1") (pin "31") (pinfunction "31_31") (pintype "bidirectional"))
      (node (ref "R123") (pin "6") (pinfunction "6_6") (pintype "passive"))
    )
    (net (code "33") (name "DIO_22") (class "Default")
      (node (ref "J1") (pin "13") (pinfunction "13_13") (pintype "bidirectional"))
      (node (ref "R123") (pin "7") (pinfunction "7_7") (pintype "passive"))
    )
    (net (code "34") (name "DIO_23") (class "Default")
      (node (ref "J1") (pin "32") (pinfunction "32_32") (pintype "bidirectional"))
      (node (ref "R123") (pin "8") (pinfunction "8_8") (pintype "passive"))
    )
    (net (code "35") (name "DIO_24") (class "Default")
      (node (ref "J1") (pin "14") (pinfunction "14_14") (pintype "bidirectional"))
      (node (ref "R126") (pin "5") (pinfunction "5_5") (pintype "passive"))
    )
    (net (code "36") (name "DIO_25") (class "Default")
      (node (ref "J1") (pin "33") (pinfunction "33_33") (pintype "bidirectional"))
      (node (ref "R126") (pin "6") (pinfunction "6_6") (pintype "passive"))
    )
    (net (code "37") (name "DIO_26") (class "Default")
      (node (ref "J1") (pin "15") (pinfunction "15_15") (pintype "bidirectional"))
      (node (ref "R126") (pin "7") (pinfunction "7_7") (pintype "passive"))
    )
    (net (code "38") (name "DIO_27") (class "Default")
      (node (ref "J1") (pin "34") (pinfunction "34_34") (pintype "bidirectional"))
      (node (ref "R126") (pin "8") (pinfunction "8_8") (pintype "passive"))
    )
    (net (code "39") (name "DIO_28") (class "Default")
      (node (ref "J1") (pin "16") (pinfunction "16_16") (pintype "bidirectional"))
      (node (ref "R125") (pin "5") (pinfunction "5_5") (pintype "passive"))
    )
    (net (code "40") (name "DIO_29") (class "Default")
      (node (ref "J1") (pin "35") (pinfunction "35_35") (pintype "bidirectional"))
      (node (ref "R125") (pin "6") (pinfunction "6_6") (pintype "passive"))
    )
    (net (code "41") (name "DIO_30") (class "Default")
      (node (ref "J1") (pin "17") (pinfunction "17_17") (pintype "bidirectional"))
      (node (ref "R125") (pin "7") (pinfunction "7_7") (pintype "passive"))
    )
    (net (code "42") (name "DIO_31") (class "Default")
      (node (ref "J1") (pin "36") (pinfunction "36_36") (pintype "bidirectional"))
      (node (ref "R125") (pin "8") (pinfunction "8_8") (pintype "passive"))
    )
    (net (code "43") (name "DIO_EN") (class "Default")
      (node (ref "DIO_EN") (pin "TP") (pinfunction "P$1_TP") (pintype "bidirectional"))
      (node (ref "IC2") (pin "12") (pinfunction "GPIO9_12") (pintype "bidirectional"))
      (node (ref "IC32") (pin "20") (pinfunction "EN_20") (pintype "bidirectional"))
      (node (ref "IC33") (pin "20") (pinfunction "EN_20") (pintype "bidirectional"))
      (node (ref "IC34") (pin "20") (pinfunction "EN_20") (pintype "bidirectional"))
      (node (ref "IC35") (pin "20") (pinfunction "EN_20") (pintype "bidirectional"))
      (node (ref "R10") (pin "2") (pinfunction "2_2") (pintype "passive"))
      (node (ref "R11") (pin "2") (pinfunction "2_2") (pintype "passive"))
      (node (ref "R127") (pin "2") (pinfunction "2_2") (pintype "passive"))
      (node (ref "R8") (pin "2") (pinfunction "2_2") (pintype "passive"))
      (node (ref "X3") (pin "A11") (pinfunction "11_A11") (pintype "passive"))
    )
    (net (code "44") (name "DIO_LEVEL_SELECT") (class "Default")
      (node (ref "DIO_LS") (pin "TP") (pinfunction "P$1_TP") (pintype "bidirectional"))
      (node (ref "IC2") (pin "9") (pinfunction "GPIO7_9") (pintype "bidirectional"))
      (node (ref "IC38") (pin "7") (pinfunction "1C_7") (pintype "input"))
      (node (ref "IC39") (pin "2") (pinfunction "IN_2") (pintype "bidirectional"))
      (node (ref "X3") (pin "A13") (pinfunction "13_A13") (pintype "passive"))
    )
    (net (code "45") (name "DIO_RESET") (class "Default")
      (node (ref "DIO_RST") (pin "TP") (pinfunction "P$1_TP") (pintype "bidirectional"))
      (node (ref "IC2") (pin "11") (pinfunction "GPIO8_11") (pintype "bidirectional"))
      (node (ref "IC36") (pin "13") (pinfunction "~{RESET}_13") (pintype "input"))
      (node (ref "IC37") (pin "13") (pinfunction "~{RESET}_13") (pintype "input"))
      (node (ref "X3") (pin "A12") (pinfunction "12_A12") (pintype "passive"))
    )
    (net (code "46") (name "EXT") (class "Default")
      (node (ref "J1") (pin "1") (pinfunction "1_1") (pintype "bidirectional"))
      (node (ref "J1") (pin "20") (pinfunction "20_20") (pintype "bidirectional"))
      (node (ref "JP-EXT-1") (pin "2") (pinfunction "2_2") (pintype "passive"))
      (node (ref "JP-EXT-2") (pin "2") (pinfunction "2_2") (pintype "passive"))
    )
    (net (code "47") (name "GND") (class "Default")
      (node (ref "C1") (pin "2") (pinfunction "2_2") (pintype "passive"))
      (node (ref "C112") (pin "2") (pinfunction "2_2") (pintype "passive"))
      (node (ref "C113") (pin "2") (pinfunction "2_2") (pintype "passive"))
      (node (ref "C114") (pin "2") (pinfunction "2_2") (pintype "passive"))
      (node (ref "C115") (pin "2") (pinfunction "2_2") (pintype "passive"))
      (node (ref "C116") (pin "2") (pinfunction "2_2") (pintype "passive"))
      (node (ref "C120") (pin "2") (pinfunction "2_2") (pintype "passive"))
      (node (ref "C121") (pin "2") (pinfunction "2_2") (pintype "passive"))
      (node (ref "C151") (pin "2") (pinfunction "2_2") (pintype "passive"))
      (node (ref "C152") (pin "2") (pinfunction "2_2") (pintype "passive"))
      (node (ref "C153") (pin "2") (pinfunction "2_2") (pintype "passive"))
      (node (ref "C154") (pin "2") (pinfunction "2_2") (pintype "passive"))
      (node (ref "C155") (pin "2") (pinfunction "2_2") (pintype "passive"))
      (node (ref "C156") (pin "2") (pinfunction "2_2") (pintype "passive"))
      (node (ref "C157") (pin "2") (pinfunction "2_2") (pintype "passive"))
      (node (ref "C158") (pin "2") (pinfunction "2_2") (pintype "passive"))
      (node (ref "C159") (pin "2") (pinfunction "2_2") (pintype "passive"))
      (node (ref "C160") (pin "2") (pinfunction "2_2") (pintype "passive"))
      (node (ref "C161") (pin "2") (pinfunction "2_2") (pintype "passive"))
      (node (ref "C162") (pin "2") (pinfunction "2_2") (pintype "passive"))
      (node (ref "C163") (pin "2") (pinfunction "2_2") (pintype "passive"))
      (node (ref "C164") (pin "2") (pinfunction "2_2") (pintype "passive"))
      (node (ref "C165") (pin "2") (pinfunction "2_2") (pintype "passive"))
      (node (ref "C166") (pin "2") (pinfunction "2_2") (pintype "passive"))
      (node (ref "C167") (pin "2") (pinfunction "2_2") (pintype "passive"))
      (node (ref "C168") (pin "2") (pinfunction "2_2") (pintype "passive"))
      (node (ref "C169") (pin "2") (pinfunction "2_2") (pintype "passive"))
      (node (ref "C170") (pin "2") (pinfunction "2_2") (pintype "passive"))
      (node (ref "C171") (pin "2") (pinfunction "2_2") (pintype "passive"))
      (node (ref "C2") (pin "2") (pinfunction "2_2") (pintype "passive"))
      (node (ref "C26") (pin "2") (pinfunction "2_2") (pintype "passive"))
      (node (ref "C27") (pin "2") (pinfunction "2_2") (pintype "passive"))
      (node (ref "C3") (pin "2") (pinfunction "2_2") (pintype "passive"))
      (node (ref "C4") (pin "2") (pinfunction "2_2") (pintype "passive"))
      (node (ref "C5") (pin "2") (pinfunction "2_2") (pintype "passive"))
      (node (ref "C6") (pin "2") (pinfunction "2_2") (pintype "passive"))
      (node (ref "C77") (pin "2") (pinfunction "2_2") (pintype "passive"))
      (node (ref "C78") (pin "2") (pinfunction "2_2") (pintype "passive"))
      (node (ref "C79") (pin "2") (pinfunction "2_2") (pintype "passive"))
      (node (ref "C80") (pin "2") (pinfunction "2_2") (pintype "passive"))
      (node (ref "C81") (pin "2") (pinfunction "2_2") (pintype "passive"))
      (node (ref "C82") (pin "2") (pinfunction "2_2") (pintype "passive"))
      (node (ref "C83") (pin "2") (pinfunction "2_2") (pintype "passive"))
      (node (ref "C84") (pin "2") (pinfunction "2_2") (pintype "passive"))
      (node (ref "C87") (pin "2") (pinfunction "2_2") (pintype "passive"))
      (node (ref "C88") (pin "2") (pinfunction "2_2") (pintype "passive"))
      (node (ref "C89") (pin "2") (pinfunction "2_2") (pintype "passive"))
      (node (ref "DBG1") (pin "2") (pinfunction "P$2_2") (pintype "bidirectional"))
      (node (ref "DBG1") (pin "4") (pinfunction "P$4_4") (pintype "bidirectional"))
      (node (ref "DBG2") (pin "2") (pinfunction "P$2_2") (pintype "bidirectional"))
      (node (ref "DBG2") (pin "4") (pinfunction "P$4_4") (pintype "bidirectional"))
      (node (ref "DIO_GND") (pin "TP") (pinfunction "P$1_TP") (pintype "bidirectional"))
      (node (ref "ESD1") (pin "1") (pinfunction "A_1") (pintype "bidirectional"))
      (node (ref "IC1") (pin "2") (pinfunction "GND_2") (pintype "bidirectional"))
      (node (ref "IC2") (pin "19") (pinfunction "TESTEN_19") (pintype "bidirectional"))
      (node (ref "IC2") (pin "57") (pinfunction "GND_57") (pintype "bidirectional"))
      (node (ref "IC3") (pin "5") (pinfunction "V-_5") (pintype "power_in"))
      (node (ref "IC32") (pin "1") (pinfunction "GND_1") (pintype "power_in"))
      (node (ref "IC32") (pin "PAD") (pinfunction "GND_PAD") (pintype "power_in"))
      (node (ref "IC33") (pin "1") (pinfunction "GND_1") (pintype "power_in"))
      (node (ref "IC33") (pin "PAD") (pinfunction "GND_PAD") (pintype "power_in"))
      (node (ref "IC34") (pin "1") (pinfunction "GND_1") (pintype "power_in"))
      (node (ref "IC34") (pin "PAD") (pinfunction "GND_PAD") (pintype "power_in"))
      (node (ref "IC35") (pin "1") (pinfunction "GND_1") (pintype "power_in"))
      (node (ref "IC35") (pin "PAD") (pinfunction "GND_PAD") (pintype "power_in"))
      (node (ref "IC36") (pin "23") (pinfunction "VSS_23") (pintype "power_in"))
      (node (ref "IC36") (pin "25") (pinfunction "VSS_25") (pintype "power_in"))
      (node (ref "IC37") (pin "23") (pinfunction "VSS_23") (pintype "power_in"))
      (node (ref "IC37") (pin "25") (pinfunction "VSS_25") (pintype "power_in"))
      (node (ref "IC38") (pin "4") (pinfunction "GND_4") (pintype "power_in"))
      (node (ref "IC39") (pin "3") (pinfunction "V-_3") (pintype "bidirectional"))
      (node (ref "IC4") (pin "4") (pinfunction "GND_4") (pintype "power_in"))
      (node (ref "J1") (pin "18") (pinfunction "18_18") (pintype "bidirectional"))
      (node (ref "J1") (pin "19") (pinfunction "19_19") (pintype "bidirectional"))
      (node (ref "J1") (pin "MH1") (pinfunction "MH1_MH1") (pintype "bidirectional"))
      (node (ref "J1") (pin "MH2") (pinfunction "MH2_MH2") (pintype "bidirectional"))
      (node (ref "R23") (pin "2") (pinfunction "2_2") (pintype "passive"))
      (node (ref "R5") (pin "2") (pinfunction "2_2") (pintype "passive"))
      (node (ref "R61") (pin "2") (pinfunction "2_2") (pintype "passive"))
      (node (ref "R62") (pin "2") (pinfunction "2_2") (pintype "passive"))
      (node (ref "R64") (pin "2") (pinfunction "2_2") (pintype "passive"))
      (node (ref "R68") (pin "2") (pinfunction "2_2") (pintype "passive"))
      (node (ref "R77") (pin "1") (pinfunction "1_1") (pintype "passive"))
      (node (ref "REF1") (pin "2") (pinfunction "A_2") (pintype "passive"))
      (node (ref "REF1") (pin "3") (pinfunction "A_3") (pintype "passive"))
      (node (ref "RESET") (pin "2") (pinfunction "S_2") (pintype "passive"))
      (node (ref "USBC") (pin "A1") (pinfunction "GND_A1") (pintype "passive"))
      (node (ref "USBC") (pin "A12") (pinfunction "GND1_A12") (pintype "passive"))
      (node (ref "USBC") (pin "B1") (pinfunction "GND3_B1") (pintype "passive"))
      (node (ref "USBC") (pin "B12") (pinfunction "GND2_B12") (pintype "passive"))
      (node (ref "USB_BOOT") (pin "2") (pinfunction "S_2") (pintype "passive"))
      (node (ref "X1") (pin "2") (pinfunction "VSS_2") (pintype "power_in"))
      (node (ref "X1") (pin "4") (pinfunction "VDD_4") (pintype "power_in"))
      (node (ref "X3") (pin "A10") (pinfunction "10_A10") (pintype "passive"))
      (node (ref "X3") (pin "A14") (pinfunction "14_A14") (pintype "passive"))
      (node (ref "X3") (pin "A15") (pinfunction "15_A15") (pintype "passive"))
      (node (ref "X3") (pin "A16") (pinfunction "16_A16") (pintype "passive"))
      (node (ref "X3") (pin "A25") (pinfunction "25_A25") (pintype "passive"))
      (node (ref "X3") (pin "A30") (pinfunction "30_A30") (pintype "passive"))
      (node (ref "X3") (pin "A31") (pinfunction "31_A31") (pintype "passive"))
      (node (ref "X3") (pin "A32") (pinfunction "32_A32") (pintype "passive"))
      (node (ref "X3") (pin "B10") (pinfunction "10_B10") (pintype "passive"))
      (node (ref "X3") (pin "B14") (pinfunction "14_B14") (pintype "passive"))
      (node (ref "X3") (pin "B15") (pinfunction "15_B15") (pintype "passive"))
      (node (ref "X3") (pin "B16") (pinfunction "16_B16") (pintype "passive"))
      (node (ref "X3") (pin "B19") (pinfunction "19_B19") (pintype "passive"))
      (node (ref "X3") (pin "B22") (pinfunction "22_B22") (pintype "passive"))
      (node (ref "X3") (pin "B25") (pinfunction "25_B25") (pintype "passive"))
      (node (ref "X3") (pin "B30") (pinfunction "30_B30") (pintype "passive"))
      (node (ref "X3") (pin "B31") (pinfunction "31_B31") (pintype "passive"))
      (node (ref "X3") (pin "B32") (pinfunction "32_B32") (pintype "passive"))
    )
    (net (code "48") (name "Net-(IC2-USB_DM)") (class "Default")
      (node (ref "IC2") (pin "46") (pinfunction "USB_DM_46") (pintype "bidirectional"))
      (node (ref "R6") (pin "2") (pinfunction "2_2") (pintype "passive"))
    )
    (net (code "49") (name "Net-(IC2-USB_DP)") (class "Default")
      (node (ref "IC2") (pin "47") (pinfunction "USB_DP_47") (pintype "bidirectional"))
      (node (ref "R7") (pin "2") (pinfunction "2_2") (pintype "passive"))
    )
    (net (code "50") (name "Net-(IC3-+IN)") (class "Default")
      (node (ref "C3") (pin "1") (pinfunction "1_1") (pintype "passive"))
      (node (ref "C4") (pin "1") (pinfunction "1_1") (pintype "passive"))
      (node (ref "IC3") (pin "3") (pinfunction "+IN_3") (pintype "input"))
      (node (ref "R2") (pin "1") (pinfunction "1_1") (pintype "passive"))
      (node (ref "REF1") (pin "1") (pinfunction "C_1") (pintype "passive"))
      (node (ref "VREF1") (pin "TP") (pinfunction "P$1_TP") (pintype "bidirectional"))
    )
    (net (code "51") (name "Net-(IC32-A1)") (class "Default")
      (node (ref "IC32") (pin "3") (pinfunction "A1_3") (pintype "bidirectional"))
      (node (ref "IC36") (pin "22") (pinfunction "GPA7_22") (pintype "bidirectional"))
    )
    (net (code "52") (name "Net-(IC32-A2)") (class "Default")
      (node (ref "IC32") (pin "4") (pinfunction "A2_4") (pintype "bidirectional"))
      (node (ref "IC36") (pin "21") (pinfunction "GPA6_21") (pintype "bidirectional"))
    )
    (net (code "53") (name "Net-(IC32-A3)") (class "Default")
      (node (ref "IC32") (pin "5") (pinfunction "A3_5") (pintype "bidirectional"))
      (node (ref "IC36") (pin "20") (pinfunction "GPA5_20") (pintype "bidirectional"))
    )
    (net (code "54") (name "Net-(IC32-A4)") (class "Default")
      (node (ref "IC32") (pin "6") (pinfunction "A4_6") (pintype "bidirectional"))
      (node (ref "IC36") (pin "19") (pinfunction "GPA4_19") (pintype "bidirectional"))
    )
    (net (code "55") (name "Net-(IC32-A5)") (class "Default")
      (node (ref "IC32") (pin "7") (pinfunction "A5_7") (pintype "bidirectional"))
      (node (ref "IC36") (pin "18") (pinfunction "GPA3_18") (pintype "bidirectional"))
    )
    (net (code "56") (name "Net-(IC32-A6)") (class "Default")
      (node (ref "IC32") (pin "8") (pinfunction "A6_8") (pintype "bidirectional"))
      (node (ref "IC36") (pin "17") (pinfunction "GPA2_17") (pintype "bidirectional"))
    )
    (net (code "57") (name "Net-(IC32-A7)") (class "Default")
      (node (ref "IC32") (pin "9") (pinfunction "A7_9") (pintype "bidirectional"))
      (node (ref "IC36") (pin "16") (pinfunction "GPA1_16") (pintype "bidirectional"))
    )
    (net (code "58") (name "Net-(IC32-A8)") (class "Default")
      (node (ref "IC32") (pin "10") (pinfunction "A8_10") (pintype "bidirectional"))
      (node (ref "IC36") (pin "15") (pinfunction "GPA0_15") (pintype "bidirectional"))
    )
    (net (code "59") (name "Net-(IC32-B1)") (class "Default")
      (node (ref "IC32") (pin "18") (pinfunction "B1_18") (pintype "bidirectional"))
      (node (ref "R119") (pin "1") (pinfunction "1_1") (pintype "passive"))
    )
    (net (code "60") (name "Net-(IC32-B2)") (class "Default")
      (node (ref "IC32") (pin "17") (pinfunction "B2_17") (pintype "bidirectional"))
      (node (ref "R119") (pin "2") (pinfunction "2_2") (pintype "passive"))
    )
    (net (code "61") (name "Net-(IC32-B3)") (class "Default")
      (node (ref "IC32") (pin "16") (pinfunction "B3_16") (pintype "bidirectional"))
      (node (ref "R119") (pin "3") (pinfunction "3_3") (pintype "passive"))
    )
    (net (code "62") (name "Net-(IC32-B4)") (class "Default")
      (node (ref "IC32") (pin "15") (pinfunction "B4_15") (pintype "bidirectional"))
      (node (ref "R119") (pin "4") (pinfunction "4_4") (pintype "passive"))
    )
    (net (code "63") (name "Net-(IC32-B5)") (class "Default")
      (node (ref "IC32") (pin "14") (pinfunction "B5_14") (pintype "bidirectional"))
      (node (ref "R120") (pin "1") (pinfunction "1_1") (pintype "passive"))
    )
    (net (code "64") (name "Net-(IC32-B6)") (class "Default")
      (node (ref "IC32") (pin "13") (pinfunction "B6_13") (pintype "bidirectional"))
      (node (ref "R120") (pin "2") (pinfunction "2_2") (pintype "passive"))
    )
    (net (code "65") (name "Net-(IC32-B7)") (class "Default")
      (node (ref "IC32") (pin "12") (pinfunction "B7_12") (pintype "bidirectional"))
      (node (ref "R120") (pin "3") (pinfunction "3_3") (pintype "passive"))
    )
    (net (code "66") (name "Net-(IC32-B8)") (class "Default")
      (node (ref "IC32") (pin "11") (pinfunction "B8_11") (pintype "bidirectional"))
      (node (ref "R120") (pin "4") (pinfunction "4_4") (pintype "passive"))
    )
    (net (code "67") (name "Net-(IC33-A1)") (class "Default")
      (node (ref "IC33") (pin "3") (pinfunction "A1_3") (pintype "bidirectional"))
      (node (ref "IC36") (pin "7") (pinfunction "GPB7_7") (pintype "bidirectional"))
    )
    (net (code "68") (name "Net-(IC33-A2)") (class "Default")
      (node (ref "IC33") (pin "4") (pinfunction "A2_4") (pintype "bidirectional"))
      (node (ref "IC36") (pin "6") (pinfunction "GPB6_6") (pintype "bidirectional"))
    )
    (net (code "69") (name "Net-(IC33-A3)") (class "Default")
      (node (ref "IC33") (pin "5") (pinfunction "A3_5") (pintype "bidirectional"))
      (node (ref "IC36") (pin "5") (pinfunction "GPB5_5") (pintype "bidirectional"))
    )
    (net (code "70") (name "Net-(IC33-A4)") (class "Default")
      (node (ref "IC33") (pin "6") (pinfunction "A4_6") (pintype "bidirectional"))
      (node (ref "IC36") (pin "4") (pinfunction "GPB4_4") (pintype "bidirectional"))
    )
    (net (code "71") (name "Net-(IC33-A5)") (class "Default")
      (node (ref "IC33") (pin "7") (pinfunction "A5_7") (pintype "bidirectional"))
      (node (ref "IC36") (pin "3") (pinfunction "GPB3_3") (pintype "bidirectional"))
    )
    (net (code "72") (name "Net-(IC33-A6)") (class "Default")
      (node (ref "IC33") (pin "8") (pinfunction "A6_8") (pintype "bidirectional"))
      (node (ref "IC36") (pin "2") (pinfunction "GPB2_2") (pintype "bidirectional"))
    )
    (net (code "73") (name "Net-(IC33-A7)") (class "Default")
      (node (ref "IC33") (pin "9") (pinfunction "A7_9") (pintype "bidirectional"))
      (node (ref "IC36") (pin "1") (pinfunction "GPB1_1") (pintype "bidirectional"))
    )
    (net (code "74") (name "Net-(IC33-A8)") (class "Default")
      (node (ref "IC33") (pin "10") (pinfunction "A8_10") (pintype "bidirectional"))
      (node (ref "IC36") (pin "24") (pinfunction "GPB0_24") (pintype "bidirectional"))
    )
    (net (code "75") (name "Net-(IC33-B1)") (class "Default")
      (node (ref "IC33") (pin "18") (pinfunction "B1_18") (pintype "bidirectional"))
      (node (ref "R121") (pin "1") (pinfunction "1_1") (pintype "passive"))
    )
    (net (code "76") (name "Net-(IC33-B2)") (class "Default")
      (node (ref "IC33") (pin "17") (pinfunction "B2_17") (pintype "bidirectional"))
      (node (ref "R121") (pin "2") (pinfunction "2_2") (pintype "passive"))
    )
    (net (code "77") (name "Net-(IC33-B3)") (class "Default")
      (node (ref "IC33") (pin "16") (pinfunction "B3_16") (pintype "bidirectional"))
      (node (ref "R121") (pin "3") (pinfunction "3_3") (pintype "passive"))
    )
    (net (code "78") (name "Net-(IC33-B4)") (class "Default")
      (node (ref "IC33") (pin "15") (pinfunction "B4_15") (pintype "bidirectional"))
      (node (ref "R121") (pin "4") (pinfunction "4_4") (pintype "passive"))
    )
    (net (code "79") (name "Net-(IC33-B5)") (class "Default")
      (node (ref "IC33") (pin "14") (pinfunction "B5_14") (pintype "bidirectional"))
      (node (ref "R122") (pin "1") (pinfunction "1_1") (pintype "passive"))
    )
    (net (code "80") (name "Net-(IC33-B6)") (class "Default")
      (node (ref "IC33") (pin "13") (pinfunction "B6_13") (pintype "bidirectional"))
      (node (ref "R122") (pin "2") (pinfunction "2_2") (pintype "passive"))
    )
    (net (code "81") (name "Net-(IC33-B7)") (class "Default")
      (node (ref "IC33") (pin "12") (pinfunction "B7_12") (pintype "bidirectional"))
      (node (ref "R122") (pin "3") (pinfunction "3_3") (pintype "passive"))
    )
    (net (code "82") (name "Net-(IC33-B8)") (class "Default")
      (node (ref "IC33") (pin "11") (pinfunction "B8_11") (pintype "bidirectional"))
      (node (ref "R122") (pin "4") (pinfunction "4_4") (pintype "passive"))
    )
    (net (code "83") (name "Net-(IC34-A1)") (class "Default")
      (node (ref "IC34") (pin "3") (pinfunction "A1_3") (pintype "bidirectional"))
      (node (ref "IC37") (pin "22") (pinfunction "GPA7_22") (pintype "bidirectional"))
    )
    (net (code "84") (name "Net-(IC34-A2)") (class "Default")
      (node (ref "IC34") (pin "4") (pinfunction "A2_4") (pintype "bidirectional"))
      (node (ref "IC37") (pin "21") (pinfunction "GPA6_21") (pintype "bidirectional"))
    )
    (net (code "85") (name "Net-(IC34-A3)") (class "Default")
      (node (ref "IC34") (pin "5") (pinfunction "A3_5") (pintype "bidirectional"))
      (node (ref "IC37") (pin "20") (pinfunction "GPA5_20") (pintype "bidirectional"))
    )
    (net (code "86") (name "Net-(IC34-A4)") (class "Default")
      (node (ref "IC34") (pin "6") (pinfunction "A4_6") (pintype "bidirectional"))
      (node (ref "IC37") (pin "19") (pinfunction "GPA4_19") (pintype "bidirectional"))
    )
    (net (code "87") (name "Net-(IC34-A5)") (class "Default")
      (node (ref "IC34") (pin "7") (pinfunction "A5_7") (pintype "bidirectional"))
      (node (ref "IC37") (pin "18") (pinfunction "GPA3_18") (pintype "bidirectional"))
    )
    (net (code "88") (name "Net-(IC34-A6)") (class "Default")
      (node (ref "IC34") (pin "8") (pinfunction "A6_8") (pintype "bidirectional"))
      (node (ref "IC37") (pin "17") (pinfunction "GPA2_17") (pintype "bidirectional"))
    )
    (net (code "89") (name "Net-(IC34-A7)") (class "Default")
      (node (ref "IC34") (pin "9") (pinfunction "A7_9") (pintype "bidirectional"))
      (node (ref "IC37") (pin "16") (pinfunction "GPA1_16") (pintype "bidirectional"))
    )
    (net (code "90") (name "Net-(IC34-A8)") (class "Default")
      (node (ref "IC34") (pin "10") (pinfunction "A8_10") (pintype "bidirectional"))
      (node (ref "IC37") (pin "15") (pinfunction "GPA0_15") (pintype "bidirectional"))
    )
    (net (code "91") (name "Net-(IC34-B1)") (class "Default")
      (node (ref "IC34") (pin "18") (pinfunction "B1_18") (pintype "bidirectional"))
      (node (ref "R123") (pin "1") (pinfunction "1_1") (pintype "passive"))
    )
    (net (code "92") (name "Net-(IC34-B2)") (class "Default")
      (node (ref "IC34") (pin "17") (pinfunction "B2_17") (pintype "bidirectional"))
      (node (ref "R123") (pin "2") (pinfunction "2_2") (pintype "passive"))
    )
    (net (code "93") (name "Net-(IC34-B3)") (class "Default")
      (node (ref "IC34") (pin "16") (pinfunction "B3_16") (pintype "bidirectional"))
      (node (ref "R123") (pin "3") (pinfunction "3_3") (pintype "passive"))
    )
    (net (code "94") (name "Net-(IC34-B4)") (class "Default")
      (node (ref "IC34") (pin "15") (pinfunction "B4_15") (pintype "bidirectional"))
      (node (ref "R123") (pin "4") (pinfunction "4_4") (pintype "passive"))
    )
    (net (code "95") (name "Net-(IC34-B5)") (class "Default")
      (node (ref "IC34") (pin "14") (pinfunction "B5_14") (pintype "bidirectional"))
      (node (ref "R124") (pin "1") (pinfunction "1_1") (pintype "passive"))
    )
    (net (code "96") (name "Net-(IC34-B6)") (class "Default")
      (node (ref "IC34") (pin "13") (pinfunction "B6_13") (pintype "bidirectional"))
      (node (ref "R124") (pin "2") (pinfunction "2_2") (pintype "passive"))
    )
    (net (code "97") (name "Net-(IC34-B7)") (class "Default")
      (node (ref "IC34") (pin "12") (pinfunction "B7_12") (pintype "bidirectional"))
      (node (ref "R124") (pin "3") (pinfunction "3_3") (pintype "passive"))
    )
    (net (code "98") (name "Net-(IC34-B8)") (class "Default")
      (node (ref "IC34") (pin "11") (pinfunction "B8_11") (pintype "bidirectional"))
      (node (ref "R124") (pin "4") (pinfunction "4_4") (pintype "passive"))
    )
    (net (code "99") (name "Net-(IC35-A1)") (class "Default")
      (node (ref "IC35") (pin "3") (pinfunction "A1_3") (pintype "bidirectional"))
      (node (ref "IC37") (pin "7") (pinfunction "GPB7_7") (pintype "bidirectional"))
    )
    (net (code "100") (name "Net-(IC35-A2)") (class "Default")
      (node (ref "IC35") (pin "4") (pinfunction "A2_4") (pintype "bidirectional"))
      (node (ref "IC37") (pin "6") (pinfunction "GPB6_6") (pintype "bidirectional"))
    )
    (net (code "101") (name "Net-(IC35-A3)") (class "Default")
      (node (ref "IC35") (pin "5") (pinfunction "A3_5") (pintype "bidirectional"))
      (node (ref "IC37") (pin "5") (pinfunction "GPB5_5") (pintype "bidirectional"))
    )
    (net (code "102") (name "Net-(IC35-A4)") (class "Default")
      (node (ref "IC35") (pin "6") (pinfunction "A4_6") (pintype "bidirectional"))
      (node (ref "IC37") (pin "4") (pinfunction "GPB4_4") (pintype "bidirectional"))
    )
    (net (code "103") (name "Net-(IC35-A5)") (class "Default")
      (node (ref "IC35") (pin "7") (pinfunction "A5_7") (pintype "bidirectional"))
      (node (ref "IC37") (pin "3") (pinfunction "GPB3_3") (pintype "bidirectional"))
    )
    (net (code "104") (name "Net-(IC35-A6)") (class "Default")
      (node (ref "IC35") (pin "8") (pinfunction "A6_8") (pintype "bidirectional"))
      (node (ref "IC37") (pin "2") (pinfunction "GPB2_2") (pintype "bidirectional"))
    )
    (net (code "105") (name "Net-(IC35-A7)") (class "Default")
      (node (ref "IC35") (pin "9") (pinfunction "A7_9") (pintype "bidirectional"))
      (node (ref "IC37") (pin "1") (pinfunction "GPB1_1") (pintype "bidirectional"))
    )
    (net (code "106") (name "Net-(IC35-A8)") (class "Default")
      (node (ref "IC35") (pin "10") (pinfunction "A8_10") (pintype "bidirectional"))
      (node (ref "IC37") (pin "24") (pinfunction "GPB0_24") (pintype "bidirectional"))
    )
    (net (code "107") (name "Net-(IC35-B1)") (class "Default")
      (node (ref "IC35") (pin "18") (pinfunction "B1_18") (pintype "bidirectional"))
      (node (ref "R125") (pin "1") (pinfunction "1_1") (pintype "passive"))
    )
    (net (code "108") (name "Net-(IC35-B2)") (class "Default")
      (node (ref "IC35") (pin "17") (pinfunction "B2_17") (pintype "bidirectional"))
      (node (ref "R125") (pin "2") (pinfunction "2_2") (pintype "passive"))
    )
    (net (code "109") (name "Net-(IC35-B3)") (class "Default")
      (node (ref "IC35") (pin "16") (pinfunction "B3_16") (pintype "bidirectional"))
      (node (ref "R125") (pin "3") (pinfunction "3_3") (pintype "passive"))
    )
    (net (code "110") (name "Net-(IC35-B4)") (class "Default")
      (node (ref "IC35") (pin "15") (pinfunction "B4_15") (pintype "bidirectional"))
      (node (ref "R125") (pin "4") (pinfunction "4_4") (pintype "passive"))
    )
    (net (code "111") (name "Net-(IC35-B5)") (class "Default")
      (node (ref "IC35") (pin "14") (pinfunction "B5_14") (pintype "bidirectional"))
      (node (ref "R126") (pin "1") (pinfunction "1_1") (pintype "passive"))
    )
    (net (code "112") (name "Net-(IC35-B6)") (class "Default")
      (node (ref "IC35") (pin "13") (pinfunction "B6_13") (pintype "bidirectional"))
      (node (ref "R126") (pin "2") (pinfunction "2_2") (pintype "passive"))
    )
    (net (code "113") (name "Net-(IC35-B7)") (class "Default")
      (node (ref "IC35") (pin "12") (pinfunction "B7_12") (pintype "bidirectional"))
      (node (ref "R126") (pin "3") (pinfunction "3_3") (pintype "passive"))
    )
    (net (code "114") (name "Net-(IC35-B8)") (class "Default")
      (node (ref "IC35") (pin "11") (pinfunction "B8_11") (pintype "bidirectional"))
      (node (ref "R126") (pin "4") (pinfunction "4_4") (pintype "passive"))
    )
    (net (code "115") (name "Net-(X1-OUT)") (class "Default")
      (node (ref "C2") (pin "1") (pinfunction "1_1") (pintype "passive"))
      (node (ref "R1") (pin "1") (pinfunction "1_1") (pintype "passive"))
      (node (ref "R9") (pin "2") (pinfunction "2_2") (pintype "passive"))
      (node (ref "X1") (pin "3") (pinfunction "OUT_3") (pintype "output"))
    )
    (net (code "116") (name "Net-(X3A-1)") (class "Default")
      (node (ref "JP-3V3-1") (pin "2") (pinfunction "2_2") (pintype "passive"))
      (node (ref "X3") (pin "A1") (pinfunction "1_A1") (pintype "passive"))
    )
    (net (code "117") (name "Net-(X3B-1)") (class "Default")
      (node (ref "JP-3V3-2") (pin "2") (pinfunction "2_2") (pintype "passive"))
      (node (ref "X3") (pin "B1") (pinfunction "1_B1") (pintype "passive"))
    )
    (net (code "118") (name "QSPI_SCLK") (class "Default")
      (node (ref "IC2") (pin "52") (pinfunction "QSPI_SCLK_52") (pintype "bidirectional"))
      (node (ref "IC4") (pin "6") (pinfunction "CLK_6") (pintype "bidirectional"))
    )
    (net (code "119") (name "QSPI_SD0") (class "Default")
      (node (ref "IC2") (pin "53") (pinfunction "QSPI_SD0_53") (pintype "bidirectional"))
      (node (ref "IC4") (pin "5") (pinfunction "DI/IO0_5") (pintype "bidirectional"))
    )
    (net (code "120") (name "QSPI_SD1") (class "Default")
      (node (ref "IC2") (pin "55") (pinfunction "QSPI_SD1_55") (pintype "bidirectional"))
      (node (ref "IC4") (pin "2") (pinfunction "DO/IO1_2") (pintype "bidirectional"))
    )
    (net (code "121") (name "QSPI_SD2") (class "Default")
      (node (ref "IC2") (pin "54") (pinfunction "QSPI_SD2_54") (pintype "bidirectional"))
      (node (ref "IC4") (pin "3") (pinfunction "~{WP}/IO2_3") (pintype "bidirectional"))
    )
    (net (code "122") (name "QSPI_SD3") (class "Default")
      (node (ref "IC2") (pin "51") (pinfunction "QSPI_SD3_51") (pintype "bidirectional"))
      (node (ref "IC4") (pin "7") (pinfunction "~{HOLD}/IO3_7") (pintype "bidirectional"))
    )
    (net (code "123") (name "RP2040_RST") (class "Default")
      (node (ref "IC2") (pin "26") (pinfunction "RUN_26") (pintype "bidirectional"))
      (node (ref "R75") (pin "2") (pinfunction "2_2") (pintype "passive"))
      (node (ref "RESET") (pin "1") (pinfunction "P_1") (pintype "passive"))
      (node (ref "X3") (pin "B18") (pinfunction "18_B18") (pintype "passive"))
    )
    (net (code "124") (name "RP_XI") (class "Default")
      (node (ref "C1") (pin "1") (pinfunction "1_1") (pintype "passive"))
      (node (ref "IC2") (pin "20") (pinfunction "XIN_20") (pintype "bidirectional"))
      (node (ref "R9") (pin "1") (pinfunction "1_1") (pintype "passive"))
      (node (ref "X1") (pin "1") (pinfunction "CON_1") (pintype "input"))
    )
    (net (code "125") (name "RP_XO") (class "Default")
      (node (ref "IC2") (pin "21") (pinfunction "XOUT_21") (pintype "bidirectional"))
      (node (ref "R1") (pin "2") (pinfunction "2_2") (pintype "passive"))
    )
    (net (code "126") (name "SPI0_CS0") (class "Default")
      (node (ref "CS0") (pin "TP") (pinfunction "P$1_TP") (pintype "bidirectional"))
      (node (ref "IC2") (pin "7") (pinfunction "GPIO5_7") (pintype "bidirectional"))
      (node (ref "IC36") (pin "9") (pinfunction "~{CS}_9") (pintype "input"))
      (node (ref "X3") (pin "A2") (pinfunction "2_A2") (pintype "passive"))
    )
    (net (code "127") (name "SPI0_CS1") (class "Default")
      (node (ref "CS1") (pin "TP") (pinfunction "P$1_TP") (pintype "bidirectional"))
      (node (ref "IC2") (pin "8") (pinfunction "GPIO6_8") (pintype "bidirectional"))
      (node (ref "IC37") (pin "9") (pinfunction "~{CS}_9") (pintype "input"))
      (node (ref "X3") (pin "A3") (pinfunction "3_A3") (pintype "passive"))
    )
    (net (code "128") (name "SPI0_MISO") (class "Default")
      (node (ref "IC2") (pin "6") (pinfunction "GPIO4_6") (pintype "bidirectional"))
      (node (ref "IC36") (pin "12") (pinfunction "SO_12") (pintype "output"))
      (node (ref "IC37") (pin "12") (pinfunction "SO_12") (pintype "output"))
      (node (ref "MISO") (pin "TP") (pinfunction "P$1_TP") (pintype "bidirectional"))
      (node (ref "X3") (pin "A7") (pinfunction "7_A7") (pintype "passive"))
      (node (ref "X3") (pin "B7") (pinfunction "7_B7") (pintype "passive"))
    )
    (net (code "129") (name "SPI0_MOSI") (class "Default")
      (node (ref "IC2") (pin "5") (pinfunction "GPIO3_5") (pintype "bidirectional"))
      (node (ref "IC36") (pin "11") (pinfunction "SI_11") (pintype "input"))
      (node (ref "IC37") (pin "11") (pinfunction "SI_11") (pintype "input"))
      (node (ref "MOSI") (pin "TP") (pinfunction "P$1_TP") (pintype "bidirectional"))
      (node (ref "X3") (pin "A6") (pinfunction "6_A6") (pintype "passive"))
      (node (ref "X3") (pin "B6") (pinfunction "6_B6") (pintype "passive"))
    )
    (net (code "130") (name "SPI0_SCK") (class "Default")
      (node (ref "IC2") (pin "4") (pinfunction "GPIO2_4") (pintype "bidirectional"))
      (node (ref "IC36") (pin "10") (pinfunction "SCK_10") (pintype "input"))
      (node (ref "IC37") (pin "10") (pinfunction "SCK_10") (pintype "input"))
      (node (ref "SCK") (pin "TP") (pinfunction "P$1_TP") (pintype "bidirectional"))
      (node (ref "X3") (pin "A5") (pinfunction "5_A5") (pintype "passive"))
      (node (ref "X3") (pin "B5") (pinfunction "5_B5") (pintype "passive"))
    )
    (net (code "131") (name "SPI1_CS") (class "Default")
      (node (ref "IC2") (pin "16") (pinfunction "GPIO13_16") (pintype "bidirectional"))
      (node (ref "X3") (pin "A29") (pinfunction "29_A29") (pintype "passive"))
      (node (ref "X3") (pin "B29") (pinfunction "29_B29") (pintype "passive"))
    )
    (net (code "132") (name "SPI1_MISO") (class "Default")
      (node (ref "IC2") (pin "15") (pinfunction "GPIO12_15") (pintype "bidirectional"))
      (node (ref "X3") (pin "A26") (pinfunction "26_A26") (pintype "passive"))
      (node (ref "X3") (pin "B26") (pinfunction "26_B26") (pintype "passive"))
    )
    (net (code "133") (name "SPI1_MOSI") (class "Default")
      (node (ref "IC2") (pin "14") (pinfunction "GPIO11_14") (pintype "bidirectional"))
      (node (ref "X3") (pin "A27") (pinfunction "27_A27") (pintype "passive"))
      (node (ref "X3") (pin "B27") (pinfunction "27_B27") (pintype "passive"))
    )
    (net (code "134") (name "SPI1_SCK") (class "Default")
      (node (ref "IC2") (pin "13") (pinfunction "GPIO10_13") (pintype "bidirectional"))
      (node (ref "X3") (pin "A28") (pinfunction "28_A28") (pintype "passive"))
      (node (ref "X3") (pin "B28") (pinfunction "28_B28") (pintype "passive"))
    )
    (net (code "135") (name "SWCLK") (class "Default")
      (node (ref "DBG2") (pin "1") (pinfunction "P$1_1") (pintype "bidirectional"))
      (node (ref "IC2") (pin "24") (pinfunction "SWCLK_24") (pintype "bidirectional"))
      (node (ref "X3") (pin "B23") (pinfunction "23_B23") (pintype "passive"))
    )
    (net (code "136") (name "SWDIO") (class "Default")
      (node (ref "DBG2") (pin "3") (pinfunction "P$3_3") (pintype "bidirectional"))
      (node (ref "IC2") (pin "25") (pinfunction "SWDIO_25") (pintype "bidirectional"))
      (node (ref "X3") (pin "B24") (pinfunction "24_B24") (pintype "passive"))
    )
    (net (code "137") (name "UART0_RX") (class "Default")
      (node (ref "DBG1") (pin "1") (pinfunction "P$1_1") (pintype "bidirectional"))
      (node (ref "IC2") (pin "2") (pinfunction "GPIO0_2") (pintype "bidirectional"))
      (node (ref "X3") (pin "B20") (pinfunction "20_B20") (pintype "passive"))
    )
    (net (code "138") (name "UART0_TX") (class "Default")
      (node (ref "DBG1") (pin "3") (pinfunction "P$3_3") (pintype "bidirectional"))
      (node (ref "IC2") (pin "3") (pinfunction "GPIO1_3") (pintype "bidirectional"))
      (node (ref "X3") (pin "B21") (pinfunction "21_B21") (pintype "passive"))
    )
    (net (code "139") (name "USBD_N") (class "Default")
      (node (ref "ESD1") (pin "3") (pinfunction "C2_3") (pintype "bidirectional"))
      (node (ref "R6") (pin "1") (pinfunction "1_1") (pintype "passive"))
      (node (ref "USBC") (pin "A7") (pinfunction "D-1_A7") (pintype "passive"))
      (node (ref "USBC") (pin "B7") (pinfunction "D-2_B7") (pintype "passive"))
    )
    (net (code "140") (name "USBD_P") (class "Default")
      (node (ref "ESD1") (pin "2") (pinfunction "C1_2") (pintype "bidirectional"))
      (node (ref "R7") (pin "1") (pinfunction "1_1") (pintype "passive"))
      (node (ref "USBC") (pin "A6") (pinfunction "D+1_A6") (pintype "passive"))
      (node (ref "USBC") (pin "B6") (pinfunction "D+2_B6") (pintype "passive"))
    )
    (net (code "141") (name "USB_BOOT") (class "Default")
      (node (ref "R4") (pin "1") (pinfunction "1_1") (pintype "passive"))
      (node (ref "USB_BOOT") (pin "1") (pinfunction "P_1") (pintype "passive"))
    )
    (net (code "142") (name "USB_SHIELD") (class "Default")
      (node (ref "C115") (pin "1") (pinfunction "1_1") (pintype "passive"))
      (node (ref "R68") (pin "1") (pinfunction "1_1") (pintype "passive"))
      (node (ref "USBC") (pin "S1") (pinfunction "SHIELD_S1") (pintype "passive"))
      (node (ref "USBC") (pin "S2") (pinfunction "SHIELD_S2") (pintype "passive"))
      (node (ref "USBC") (pin "S3") (pinfunction "SHIELD_S3") (pintype "passive"))
      (node (ref "USBC") (pin "S4") (pinfunction "SHIELD_S4") (pintype "passive"))
    )
    (net (code "143") (name "VBUS") (class "Default")
      (node (ref "C78") (pin "1") (pinfunction "1_1") (pintype "passive"))
      (node (ref "C79") (pin "1") (pinfunction "1_1") (pintype "passive"))
      (node (ref "D1") (pin "A") (pinfunction "A_A") (pintype "passive"))
      (node (ref "ESD1") (pin "4") (pinfunction "C3_4") (pintype "bidirectional"))
      (node (ref "R5") (pin "1") (pinfunction "1_1") (pintype "passive"))
      (node (ref "R63") (pin "1") (pinfunction "1_1") (pintype "passive"))
      (node (ref "USBC") (pin "A4") (pinfunction "VBUS_A4") (pintype "passive"))
      (node (ref "USBC") (pin "A9") (pinfunction "VBUS1_A9") (pintype "passive"))
      (node (ref "USBC") (pin "B4") (pinfunction "VBUS3_B4") (pintype "passive"))
      (node (ref "USBC") (pin "B9") (pinfunction "VBUS2_B9") (pintype "passive"))
      (node (ref "VBUS") (pin "TP") (pinfunction "P$1_TP") (pintype "bidirectional"))
    )
    (net (code "144") (name "V_OUT_REF") (class "Default")
      (node (ref "C153") (pin "1") (pinfunction "1_1") (pintype "passive"))
      (node (ref "C154") (pin "1") (pinfunction "1_1") (pintype "passive"))
      (node (ref "C157") (pin "1") (pinfunction "1_1") (pintype "passive"))
      (node (ref "C158") (pin "1") (pinfunction "1_1") (pintype "passive"))
      (node (ref "C161") (pin "1") (pinfunction "1_1") (pintype "passive"))
      (node (ref "C162") (pin "1") (pinfunction "1_1") (pintype "passive"))
      (node (ref "C165") (pin "1") (pinfunction "1_1") (pintype "passive"))
      (node (ref "C166") (pin "1") (pinfunction "1_1") (pintype "passive"))
      (node (ref "DIO_VREF") (pin "TP") (pinfunction "P$1_TP") (pintype "bidirectional"))
      (node (ref "IC32") (pin "19") (pinfunction "VREF_B_19") (pintype "power_in"))
      (node (ref "IC33") (pin "19") (pinfunction "VREF_B_19") (pintype "power_in"))
      (node (ref "IC34") (pin "19") (pinfunction "VREF_B_19") (pintype "power_in"))
      (node (ref "IC35") (pin "19") (pinfunction "VREF_B_19") (pintype "power_in"))
      (node (ref "IC38") (pin "2") (pinfunction "1B_2") (pintype "bidirectional"))
      (node (ref "IC38") (pin "6") (pinfunction "2B_6") (pintype "bidirectional"))
      (node (ref "R10") (pin "1") (pinfunction "1_1") (pintype "passive"))
      (node (ref "R11") (pin "1") (pinfunction "1_1") (pintype "passive"))
      (node (ref "R127") (pin "1") (pinfunction "1_1") (pintype "passive"))
      (node (ref "R22") (pin "1") (pinfunction "1_1") (pintype "passive"))
      (node (ref "R8") (pin "1") (pinfunction "1_1") (pintype "passive"))
    )
    (net (code "145") (name "unconnected-(IC1-NC-Pad4)") (class "Default")
      (node (ref "IC1") (pin "4") (pinfunction "NC_4") (pintype "bidirectional"))
    )
    (net (code "146") (name "unconnected-(IC2-GPIO14-Pad17)") (class "Default")
      (node (ref "IC2") (pin "17") (pinfunction "GPIO14_17") (pintype "bidirectional"))
    )
    (net (code "147") (name "unconnected-(IC2-GPIO15-Pad18)") (class "Default")
      (node (ref "IC2") (pin "18") (pinfunction "GPIO15_18") (pintype "bidirectional"))
    )
    (net (code "148") (name "unconnected-(IC2-GPIO16-Pad27)") (class "Default")
      (node (ref "IC2") (pin "27") (pinfunction "GPIO16_27") (pintype "bidirectional"))
    )
    (net (code "149") (name "unconnected-(IC2-GPIO17-Pad28)") (class "Default")
      (node (ref "IC2") (pin "28") (pinfunction "GPIO17_28") (pintype "bidirectional"))
    )
    (net (code "150") (name "unconnected-(IC2-GPIO18-Pad29)") (class "Default")
      (node (ref "IC2") (pin "29") (pinfunction "GPIO18_29") (pintype "bidirectional"))
    )
    (net (code "151") (name "unconnected-(IC2-GPIO19-Pad30)") (class "Default")
      (node (ref "IC2") (pin "30") (pinfunction "GPIO19_30") (pintype "bidirectional"))
    )
    (net (code "152") (name "unconnected-(IC2-GPIO20-Pad31)") (class "Default")
      (node (ref "IC2") (pin "31") (pinfunction "GPIO20_31") (pintype "bidirectional"))
    )
    (net (code "153") (name "unconnected-(IC2-GPIO21-Pad32)") (class "Default")
      (node (ref "IC2") (pin "32") (pinfunction "GPIO21_32") (pintype "bidirectional"))
    )
    (net (code "154") (name "unconnected-(IC2-GPIO22-Pad34)") (class "Default")
      (node (ref "IC2") (pin "34") (pinfunction "GPIO22_34") (pintype "bidirectional"))
    )
    (net (code "155") (name "unconnected-(IC2-GPIO23-Pad35)") (class "Default")
      (node (ref "IC2") (pin "35") (pinfunction "GPIO23_35") (pintype "bidirectional"))
    )
    (net (code "156") (name "unconnected-(IC2-GPIO24-Pad36)") (class "Default")
      (node (ref "IC2") (pin "36") (pinfunction "GPIO24_36") (pintype "bidirectional"))
    )
    (net (code "157") (name "unconnected-(IC2-GPIO25-Pad37)") (class "Default")
      (node (ref "IC2") (pin "37") (pinfunction "GPIO25_37") (pintype "bidirectional"))
    )
    (net (code "158") (name "unconnected-(IC36-INTA-Pad14)") (class "Default")
      (node (ref "IC36") (pin "14") (pinfunction "INTA_14") (pintype "output"))
    )
    (net (code "159") (name "unconnected-(IC37-INTA-Pad14)") (class "Default")
      (node (ref "IC37") (pin "14") (pinfunction "INTA_14") (pintype "output"))
    )
    (net (code "160") (name "unconnected-(USBC-SBU1-PadA8)") (class "Default")
      (node (ref "USBC") (pin "A8") (pinfunction "SBU1_A8") (pintype "passive"))
    )
    (net (code "161") (name "unconnected-(USBC-SBU2-PadB8)") (class "Default")
      (node (ref "USBC") (pin "B8") (pinfunction "SBU2_B8") (pintype "passive"))
    )
    (net (code "162") (name "unconnected-(X3A-4-PadA4)") (class "Default")
      (node (ref "X3") (pin "A4") (pinfunction "4_A4") (pintype "passive"))
    )
    (net (code "163") (name "unconnected-(X3A-17-PadA17)") (class "Default")
      (node (ref "X3") (pin "A17") (pinfunction "17_A17") (pintype "passive"))
    )
    (net (code "164") (name "unconnected-(X3A-18-PadA18)") (class "Default")
      (node (ref "X3") (pin "A18") (pinfunction "18_A18") (pintype "passive"))
    )
    (net (code "165") (name "unconnected-(X3A-19-PadA19)") (class "Default")
      (node (ref "X3") (pin "A19") (pinfunction "19_A19") (pintype "passive"))
    )
    (net (code "166") (name "unconnected-(X3A-20-PadA20)") (class "Default")
      (node (ref "X3") (pin "A20") (pinfunction "20_A20") (pintype "passive"))
    )
    (net (code "167") (name "unconnected-(X3A-21-PadA21)") (class "Default")
      (node (ref "X3") (pin "A21") (pinfunction "21_A21") (pintype "passive"))
    )
    (net (code "168") (name "unconnected-(X3A-22-PadA22)") (class "Default")
      (node (ref "X3") (pin "A22") (pinfunction "22_A22") (pintype "passive"))
    )
    (net (code "169") (name "unconnected-(X3A-23-PadA23)") (class "Default")
      (node (ref "X3") (pin "A23") (pinfunction "23_A23") (pintype "passive"))
    )
    (net (code "170") (name "unconnected-(X3A-24-PadA24)") (class "Default")
      (node (ref "X3") (pin "A24") (pinfunction "24_A24") (pintype "passive"))
    )
    (net (code "171") (name "unconnected-(X3B-2-PadB2)") (class "Default")
      (node (ref "X3") (pin "B2") (pinfunction "2_B2") (pintype "passive"))
    )
    (net (code "172") (name "unconnected-(X3B-3-PadB3)") (class "Default")
      (node (ref "X3") (pin "B3") (pinfunction "3_B3") (pintype "passive"))
    )
    (net (code "173") (name "unconnected-(X3B-4-PadB4)") (class "Default")
      (node (ref "X3") (pin "B4") (pinfunction "4_B4") (pintype "passive"))
    )
    (net (code "174") (name "unconnected-(X3B-11-PadB11)") (class "Default")
      (node (ref "X3") (pin "B11") (pinfunction "11_B11") (pintype "passive"))
    )
    (net (code "175") (name "unconnected-(X3B-12-PadB12)") (class "Default")
      (node (ref "X3") (pin "B12") (pinfunction "12_B12") (pintype "passive"))
    )
    (net (code "176") (name "unconnected-(X3B-13-PadB13)") (class "Default")
      (node (ref "X3") (pin "B13") (pinfunction "13_B13") (pintype "passive"))
    )
    (net (code "177") (name "unconnected-(X3B-17-PadB17)") (class "Default")
      (node (ref "X3") (pin "B17") (pinfunction "17_B17") (pintype "passive"))
    )
    (net (code "178") (name "~{DIO_LEVEL_SELECT}") (class "Default")
      (node (ref "IC38") (pin "3") (pinfunction "2C_3") (pintype "input"))
      (node (ref "IC39") (pin "4") (pinfunction "OUT_4") (pintype "bidirectional"))
    )
    (net (code "179") (name "~{QSPI_SS}") (class "Default")
      (node (ref "IC2") (pin "56") (pinfunction "QSPI_SS_N_56") (pintype "bidirectional"))
      (node (ref "IC4") (pin "1") (pinfunction "~{CS}_1") (pintype "bidirectional"))
      (node (ref "R3") (pin "1") (pinfunction "1_1") (pintype "passive"))
      (node (ref "R4") (pin "2") (pinfunction "2_2") (pintype "passive"))
    )
  )
)
